# Relay-Board_Rack-PDU_2_1.net
KiCad netlist of a schematic drawn in EAGLE
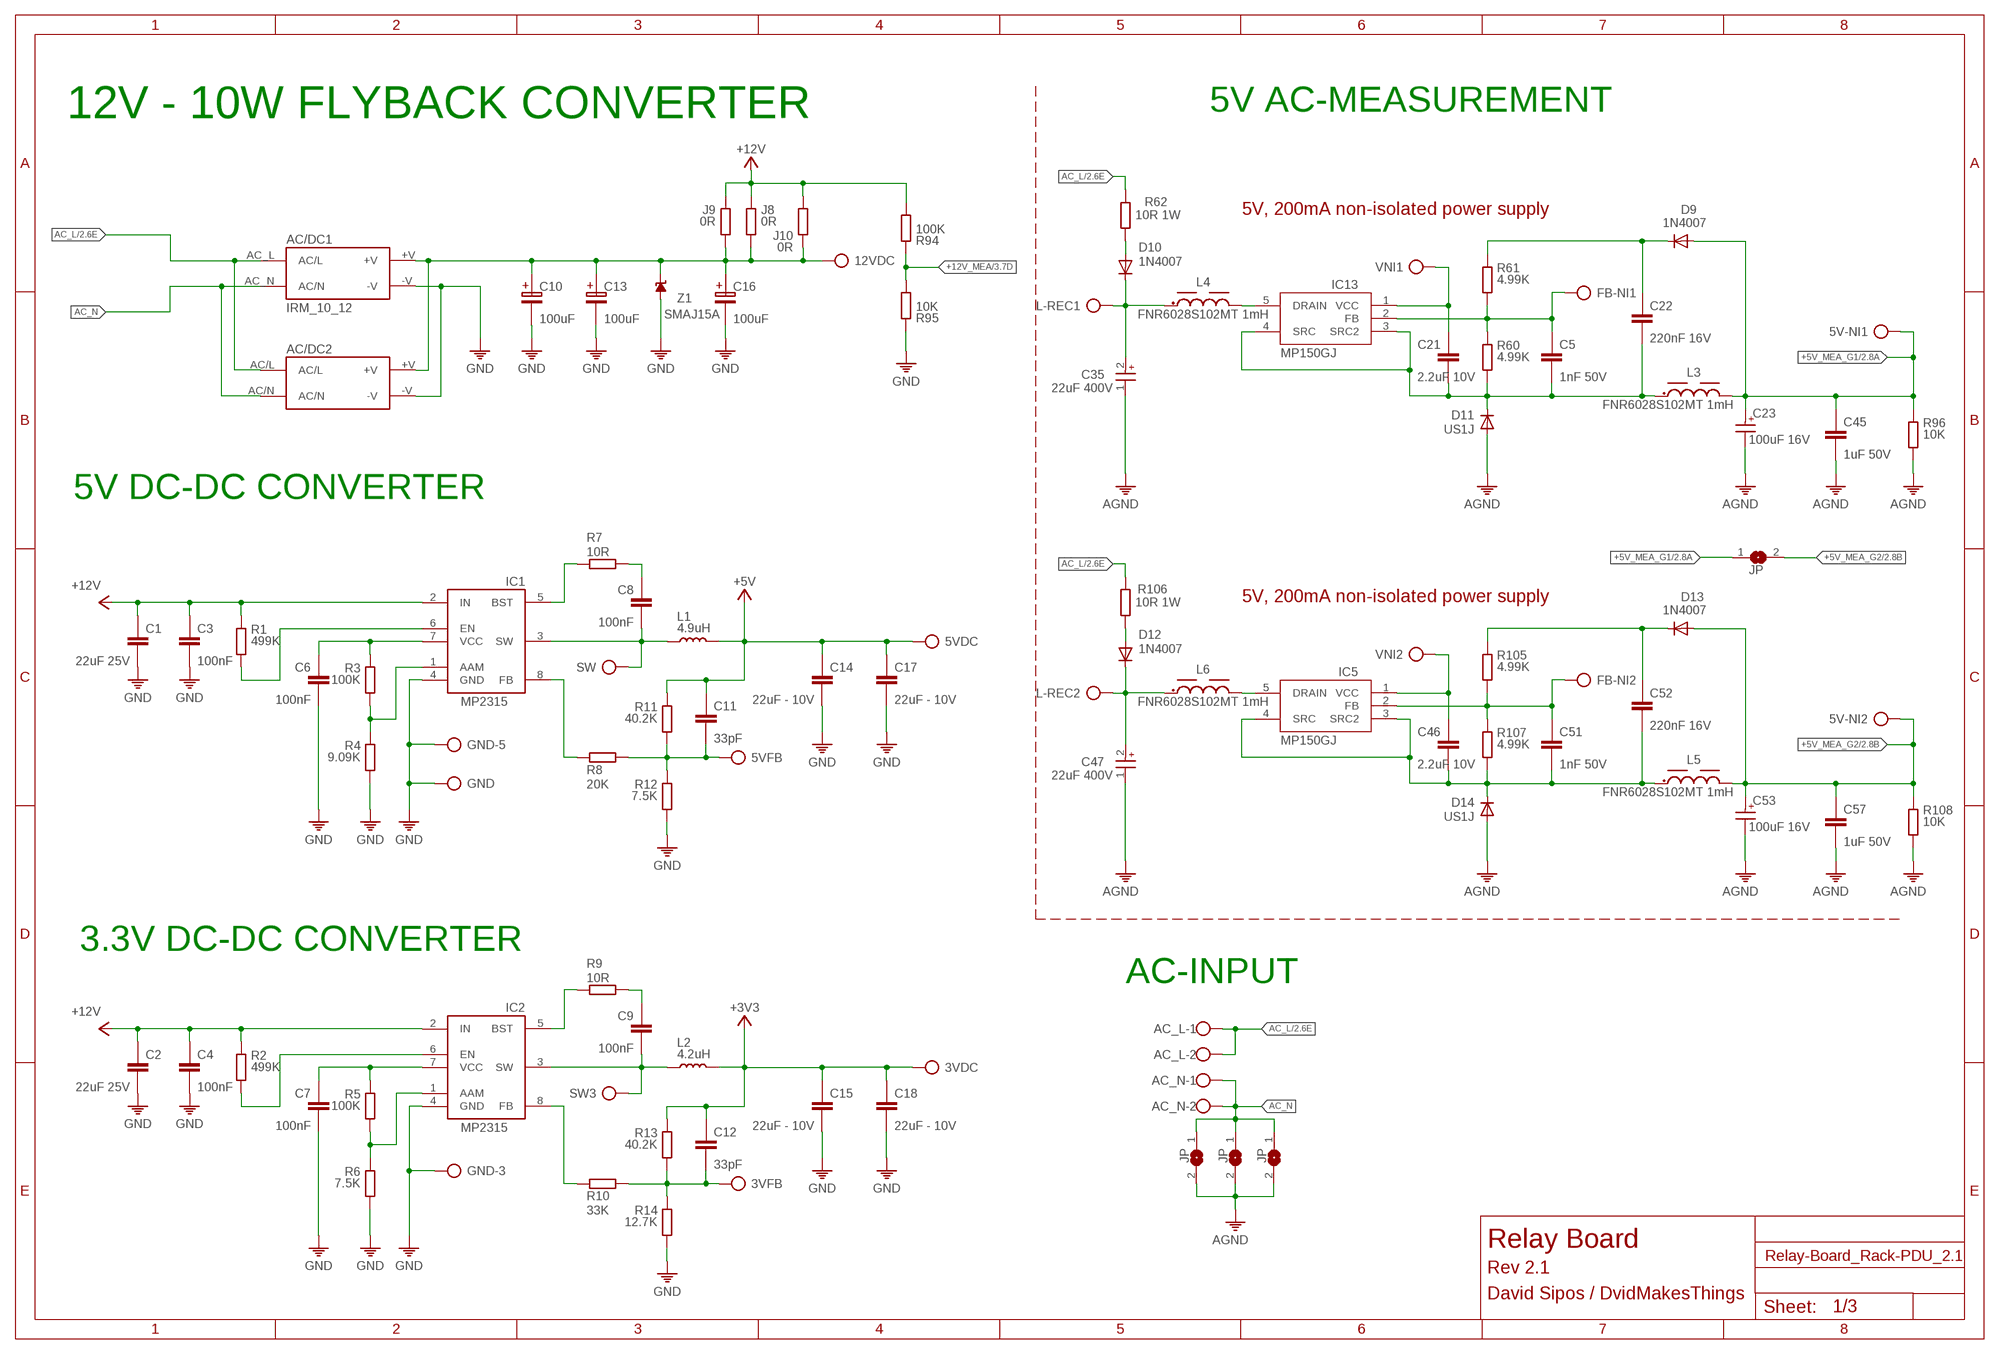
[diagram p0: schematic, sheet 1]
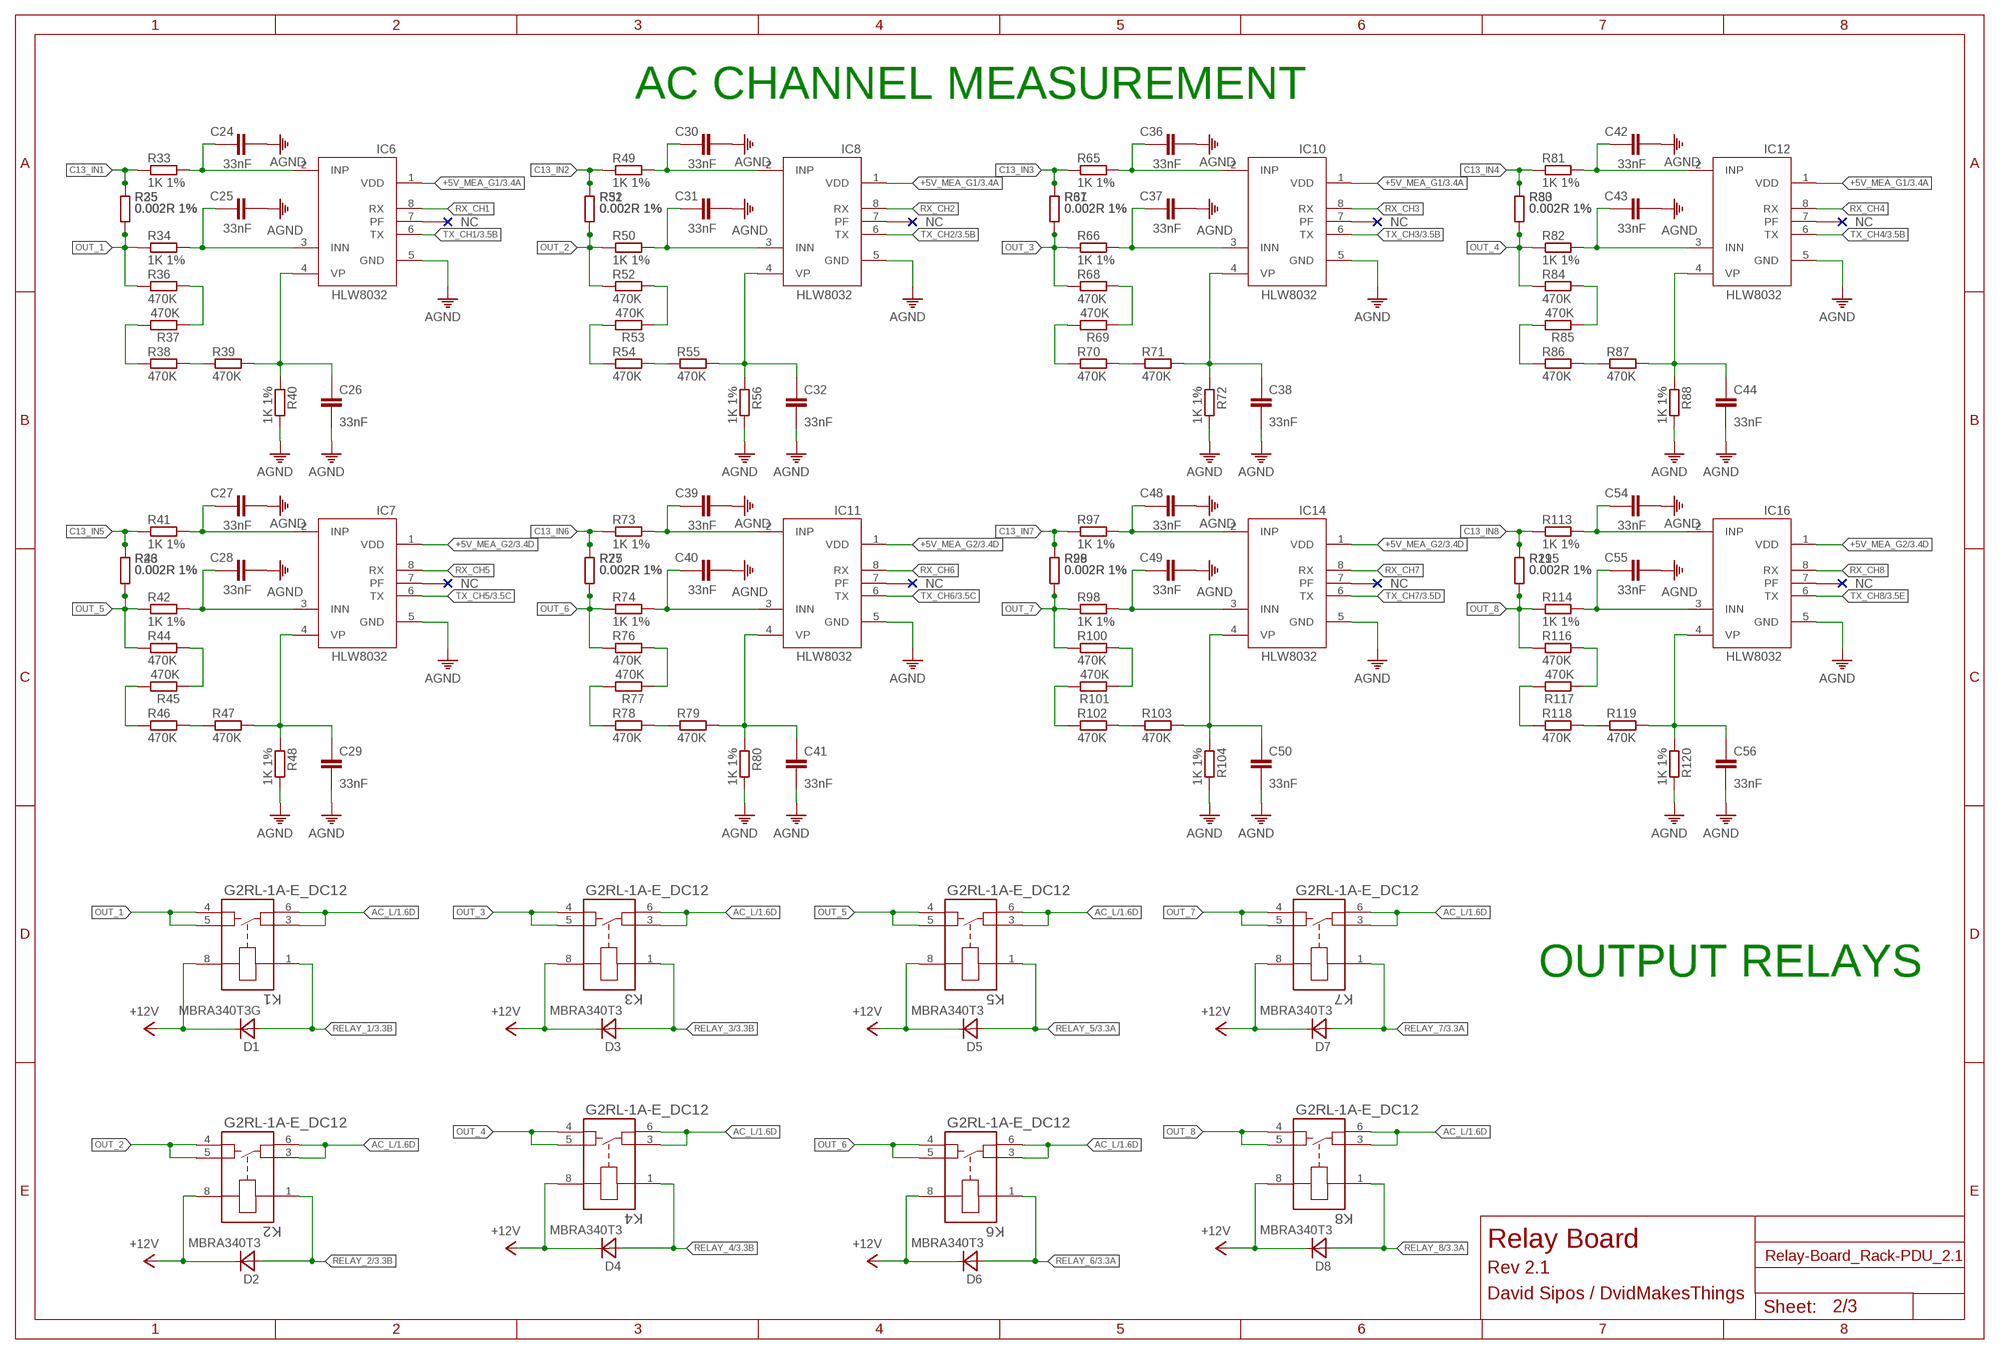
[diagram p1: schematic, sheet 2]
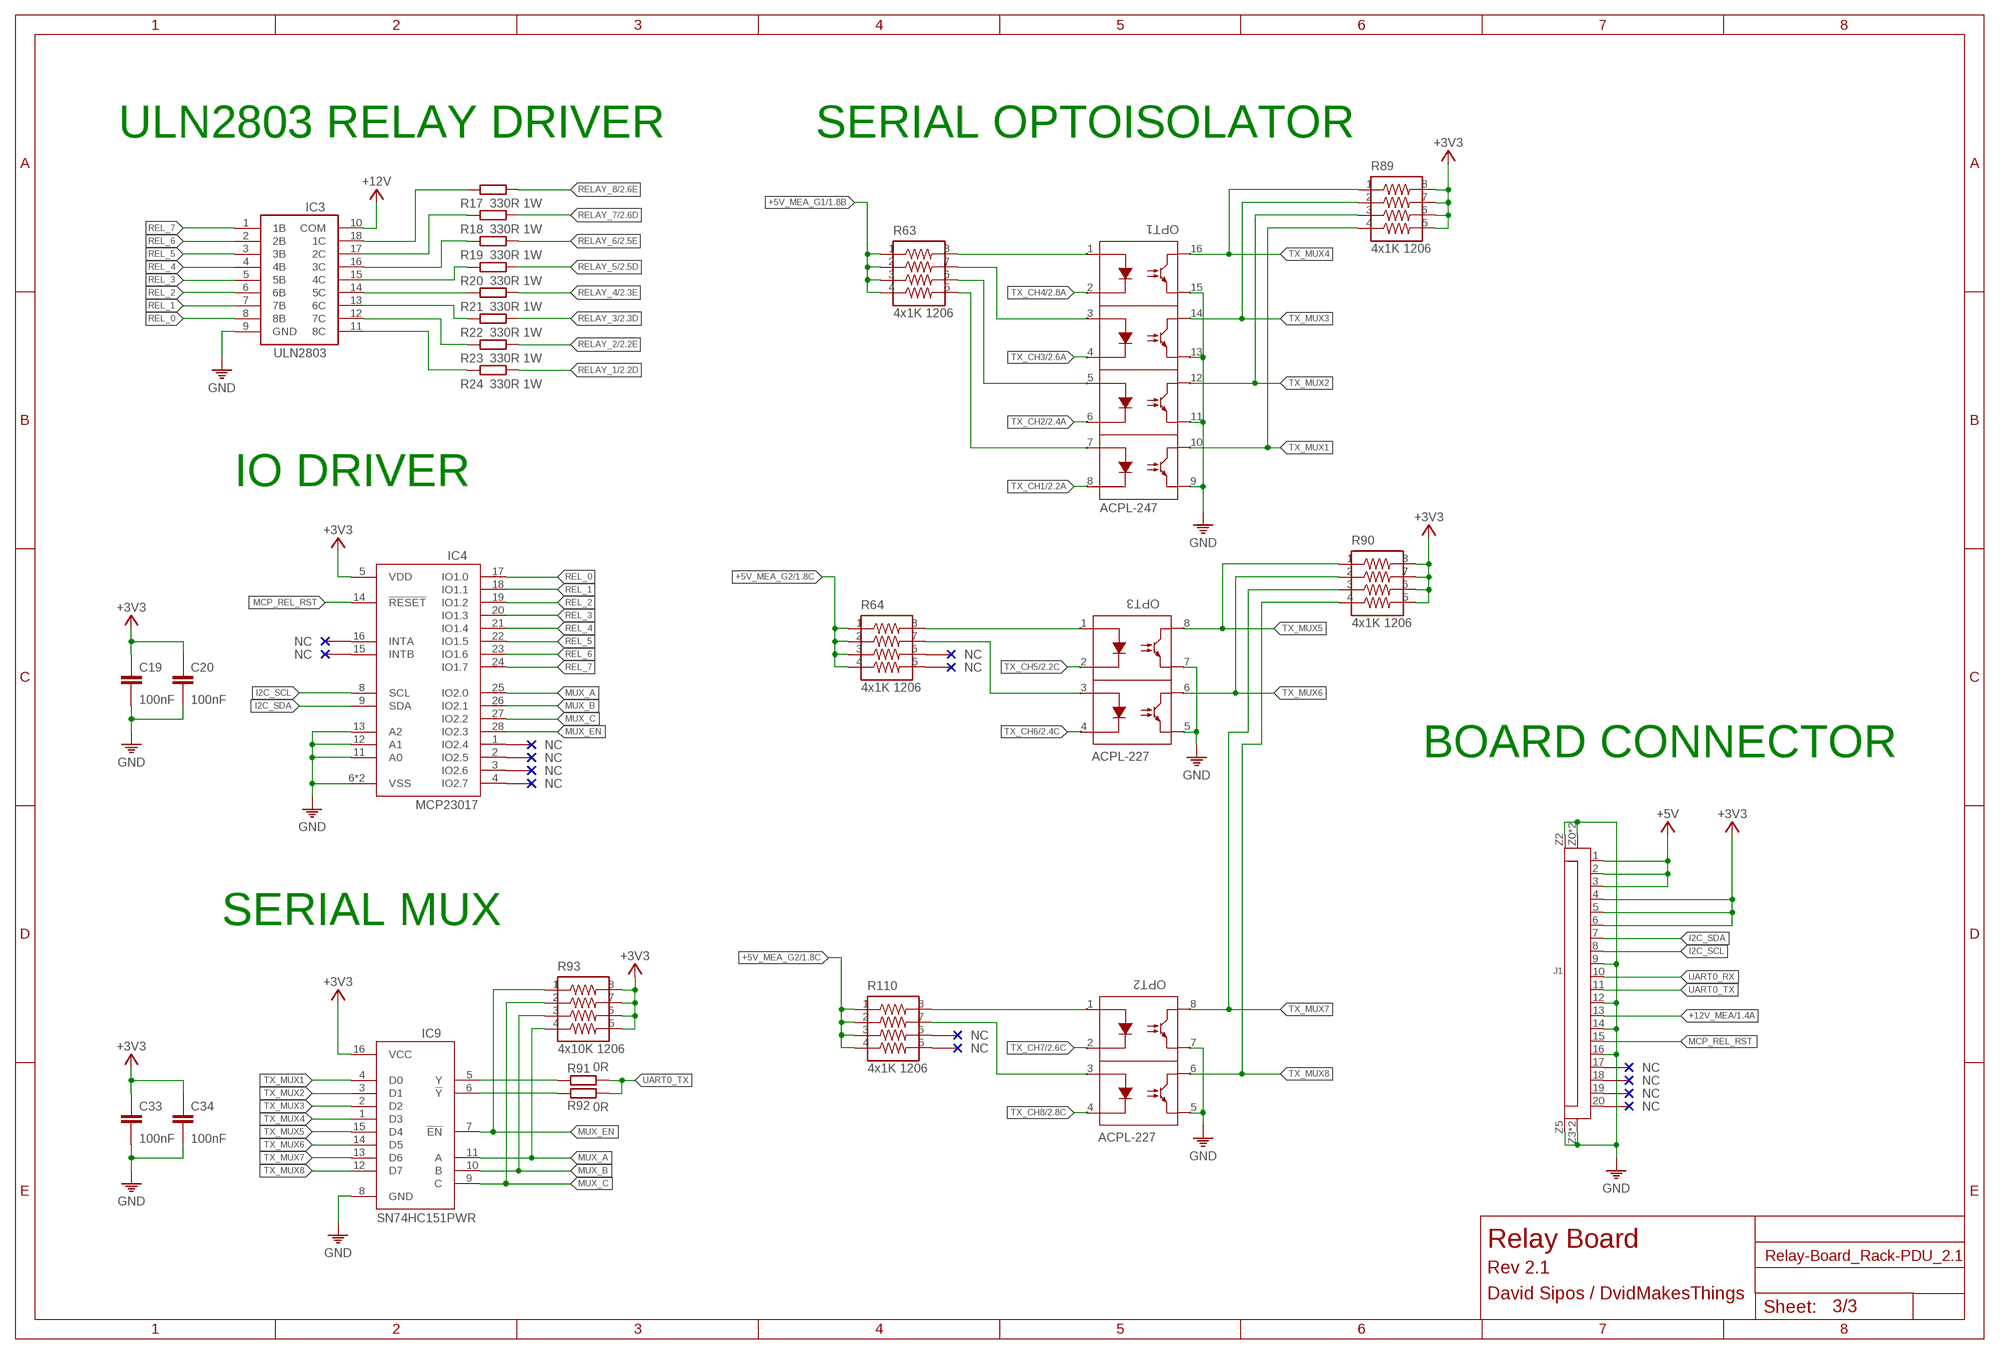
[diagram p2: schematic, sheet 3]

(export (version "E")
  (design (tool "Eeschema 10.0.6"))
  (components
    (comp (ref "C19")
      (value "100nF")
      (footprint "eagle-import:C0402")
      (libsource (lib "eagle-import") (part "C-0402"))
    )
    (comp (ref "C20")
      (value "100nF")
      (footprint "eagle-import:C0402")
      (libsource (lib "eagle-import") (part "C-0402"))
    )
    (comp (ref "C33")
      (value "100nF")
      (footprint "eagle-import:C0402")
      (libsource (lib "eagle-import") (part "C-0402"))
    )
    (comp (ref "C34")
      (value "100nF")
      (footprint "eagle-import:C0402")
      (libsource (lib "eagle-import") (part "C-0402"))
    )
    (comp (ref "IC3")
      (value "ULN2803A")
      (footprint "eagle-import:SO18")
      (libsource (lib "eagle-import") (part "ULN2803"))
    )
    (comp (ref "IC4")
      (value "MCP23017-E/ML")
      (footprint "eagle-import:QFN28[6X6]ML")
      (libsource (lib "eagle-import") (part "MCP23017-E/ML"))
    )
    (comp (ref "IC9")
      (value "SN74HC151PWR")
      (footprint "eagle-import:TSSOP16")
      (libsource (lib "eagle-import") (part "SN74HC151PWR"))
    )
    (comp (ref "J1")
      (value "FPC20-H")
      (footprint "eagle-import:FPC20")
      (libsource (lib "eagle-import") (part "FPC20-H"))
    )
    (comp (ref "OPT1")
      (value "ACPL-247")
      (footprint "eagle-import:SO16")
      (libsource (lib "eagle-import") (part "ACPL-2471"))
    )
    (comp (ref "OPT2")
      (value "ACPL-227")
      (footprint "eagle-import:SO8")
      (libsource (lib "eagle-import") (part "ACPL-227"))
    )
    (comp (ref "OPT3")
      (value "ACPL-227")
      (footprint "eagle-import:SO8")
      (libsource (lib "eagle-import") (part "ACPL-227"))
    )
    (comp (ref "R17")
      (value "330R 1W")
      (footprint "eagle-import:2512")
      (libsource (lib "eagle-import") (part "R2512"))
    )
    (comp (ref "R18")
      (value "330R 1W")
      (footprint "eagle-import:2512")
      (libsource (lib "eagle-import") (part "R2512"))
    )
    (comp (ref "R19")
      (value "330R 1W")
      (footprint "eagle-import:2512")
      (libsource (lib "eagle-import") (part "R2512"))
    )
    (comp (ref "R20")
      (value "330R 1W")
      (footprint "eagle-import:2512")
      (libsource (lib "eagle-import") (part "R2512"))
    )
    (comp (ref "R21")
      (value "330R 1W")
      (footprint "eagle-import:2512")
      (libsource (lib "eagle-import") (part "R2512"))
    )
    (comp (ref "R22")
      (value "330R 1W")
      (footprint "eagle-import:2512")
      (libsource (lib "eagle-import") (part "R2512"))
    )
    (comp (ref "R23")
      (value "330R 1W")
      (footprint "eagle-import:2512")
      (libsource (lib "eagle-import") (part "R2512"))
    )
    (comp (ref "R24")
      (value "330R 1W")
      (footprint "eagle-import:2512")
      (libsource (lib "eagle-import") (part "R2512"))
    )
    (comp (ref "R63")
      (value "4x1K 1206")
      (footprint "eagle-import:742C083103JP")
      (fields
        (field (name "MANUFACTURER") "CTS Resistor Products")
        (field (name "MPN") "742C083103JP")
        (field (name "CREATED_BY") "PCBLayout.com")
      )
      (libsource (lib "eagle-import") (part "742C083103JP"))
    )
    (comp (ref "R64")
      (value "4x1K 1206")
      (footprint "eagle-import:742C083103JP")
      (fields
        (field (name "MANUFACTURER") "CTS Resistor Products")
        (field (name "MPN") "742C083103JP")
        (field (name "CREATED_BY") "PCBLayout.com")
      )
      (libsource (lib "eagle-import") (part "742C083103JP"))
    )
    (comp (ref "R89")
      (value "4x1K 1206")
      (footprint "eagle-import:742C083103JP")
      (fields
        (field (name "MANUFACTURER") "CTS Resistor Products")
        (field (name "MPN") "742C083103JP")
        (field (name "CREATED_BY") "PCBLayout.com")
      )
      (libsource (lib "eagle-import") (part "742C083103JP"))
    )
    (comp (ref "R90")
      (value "4x1K 1206")
      (footprint "eagle-import:742C083103JP")
      (fields
        (field (name "MANUFACTURER") "CTS Resistor Products")
        (field (name "MPN") "742C083103JP")
        (field (name "CREATED_BY") "PCBLayout.com")
      )
      (libsource (lib "eagle-import") (part "742C083103JP"))
    )
    (comp (ref "R91")
      (value "0R")
      (footprint "eagle-import:0402")
      (libsource (lib "eagle-import") (part "R0402"))
    )
    (comp (ref "R92")
      (value "0R")
      (footprint "eagle-import:0402")
      (libsource (lib "eagle-import") (part "R0402"))
    )
    (comp (ref "R93")
      (value "4x10K 1206")
      (footprint "eagle-import:742C083103JP")
      (fields
        (field (name "MANUFACTURER") "CTS Resistor Products")
        (field (name "MPN") "742C083103JP")
        (field (name "CREATED_BY") "PCBLayout.com")
      )
      (libsource (lib "eagle-import") (part "742C083103JP"))
    )
    (comp (ref "R110")
      (value "4x1K 1206")
      (footprint "eagle-import:742C083103JP")
      (fields
        (field (name "MANUFACTURER") "CTS Resistor Products")
        (field (name "MPN") "742C083103JP")
        (field (name "CREATED_BY") "PCBLayout.com")
      )
      (libsource (lib "eagle-import") (part "742C083103JP"))
    )
    (comp (ref "C24")
      (value "33nF")
      (footprint "eagle-import:C1206")
      (libsource (lib "eagle-import") (part "C-1206"))
    )
    (comp (ref "C25")
      (value "33nF")
      (footprint "eagle-import:C1206")
      (libsource (lib "eagle-import") (part "C-1206"))
    )
    (comp (ref "C26")
      (value "33nF")
      (footprint "eagle-import:C1206")
      (libsource (lib "eagle-import") (part "C-1206"))
    )
    (comp (ref "C27")
      (value "33nF")
      (footprint "eagle-import:C1206")
      (libsource (lib "eagle-import") (part "C-1206"))
    )
    (comp (ref "C28")
      (value "33nF")
      (footprint "eagle-import:C1206")
      (libsource (lib "eagle-import") (part "C-1206"))
    )
    (comp (ref "C29")
      (value "33nF")
      (footprint "eagle-import:C1206")
      (libsource (lib "eagle-import") (part "C-1206"))
    )
    (comp (ref "C30")
      (value "33nF")
      (footprint "eagle-import:C1206")
      (libsource (lib "eagle-import") (part "C-1206"))
    )
    (comp (ref "C31")
      (value "33nF")
      (footprint "eagle-import:C1206")
      (libsource (lib "eagle-import") (part "C-1206"))
    )
    (comp (ref "C32")
      (value "33nF")
      (footprint "eagle-import:C1206")
      (libsource (lib "eagle-import") (part "C-1206"))
    )
    (comp (ref "C36")
      (value "33nF")
      (footprint "eagle-import:C1206")
      (libsource (lib "eagle-import") (part "C-1206"))
    )
    (comp (ref "C37")
      (value "33nF")
      (footprint "eagle-import:C1206")
      (libsource (lib "eagle-import") (part "C-1206"))
    )
    (comp (ref "C38")
      (value "33nF")
      (footprint "eagle-import:C1206")
      (libsource (lib "eagle-import") (part "C-1206"))
    )
    (comp (ref "C39")
      (value "33nF")
      (footprint "eagle-import:C1206")
      (libsource (lib "eagle-import") (part "C-1206"))
    )
    (comp (ref "C40")
      (value "33nF")
      (footprint "eagle-import:C1206")
      (libsource (lib "eagle-import") (part "C-1206"))
    )
    (comp (ref "C41")
      (value "33nF")
      (footprint "eagle-import:C1206")
      (libsource (lib "eagle-import") (part "C-1206"))
    )
    (comp (ref "C42")
      (value "33nF")
      (footprint "eagle-import:C1206")
      (libsource (lib "eagle-import") (part "C-1206"))
    )
    (comp (ref "C43")
      (value "33nF")
      (footprint "eagle-import:C1206")
      (libsource (lib "eagle-import") (part "C-1206"))
    )
    (comp (ref "C44")
      (value "33nF")
      (footprint "eagle-import:C1206")
      (libsource (lib "eagle-import") (part "C-1206"))
    )
    (comp (ref "C48")
      (value "33nF")
      (footprint "eagle-import:C1206")
      (libsource (lib "eagle-import") (part "C-1206"))
    )
    (comp (ref "C49")
      (value "33nF")
      (footprint "eagle-import:C1206")
      (libsource (lib "eagle-import") (part "C-1206"))
    )
    (comp (ref "C50")
      (value "33nF")
      (footprint "eagle-import:C1206")
      (libsource (lib "eagle-import") (part "C-1206"))
    )
    (comp (ref "C54")
      (value "33nF")
      (footprint "eagle-import:C1206")
      (libsource (lib "eagle-import") (part "C-1206"))
    )
    (comp (ref "C55")
      (value "33nF")
      (footprint "eagle-import:C1206")
      (libsource (lib "eagle-import") (part "C-1206"))
    )
    (comp (ref "C56")
      (value "33nF")
      (footprint "eagle-import:C1206")
      (libsource (lib "eagle-import") (part "C-1206"))
    )
    (comp (ref "D1")
      (value "MBRA340T3G")
      (footprint "eagle-import:SMA")
      (libsource (lib "eagle-import") (part "MBRA340T3"))
    )
    (comp (ref "D2")
      (value "MBRA340T3")
      (footprint "eagle-import:SMA")
      (libsource (lib "eagle-import") (part "MBRA340T3"))
    )
    (comp (ref "D3")
      (value "MBRA340T3")
      (footprint "eagle-import:SMA")
      (libsource (lib "eagle-import") (part "MBRA340T3"))
    )
    (comp (ref "D4")
      (value "MBRA340T3")
      (footprint "eagle-import:SMA")
      (libsource (lib "eagle-import") (part "MBRA340T3"))
    )
    (comp (ref "D5")
      (value "MBRA340T3")
      (footprint "eagle-import:SMA")
      (libsource (lib "eagle-import") (part "MBRA340T3"))
    )
    (comp (ref "D6")
      (value "MBRA340T3")
      (footprint "eagle-import:SMA")
      (libsource (lib "eagle-import") (part "MBRA340T3"))
    )
    (comp (ref "D7")
      (value "MBRA340T3")
      (footprint "eagle-import:SMA")
      (libsource (lib "eagle-import") (part "MBRA340T3"))
    )
    (comp (ref "D8")
      (value "MBRA340T3")
      (footprint "eagle-import:SMA")
      (libsource (lib "eagle-import") (part "MBRA340T3"))
    )
    (comp (ref "IC6")
      (value "HLW8032")
      (footprint "eagle-import:SO8")
      (libsource (lib "eagle-import") (part "HLW8032"))
    )
    (comp (ref "IC7")
      (value "HLW8032")
      (footprint "eagle-import:SO8")
      (libsource (lib "eagle-import") (part "HLW8032"))
    )
    (comp (ref "IC8")
      (value "HLW8032")
      (footprint "eagle-import:SO8")
      (libsource (lib "eagle-import") (part "HLW8032"))
    )
    (comp (ref "IC10")
      (value "HLW8032")
      (footprint "eagle-import:SO8")
      (libsource (lib "eagle-import") (part "HLW8032"))
    )
    (comp (ref "IC11")
      (value "HLW8032")
      (footprint "eagle-import:SO8")
      (libsource (lib "eagle-import") (part "HLW8032"))
    )
    (comp (ref "IC12")
      (value "HLW8032")
      (footprint "eagle-import:SO8")
      (libsource (lib "eagle-import") (part "HLW8032"))
    )
    (comp (ref "IC14")
      (value "HLW8032")
      (footprint "eagle-import:SO8")
      (libsource (lib "eagle-import") (part "HLW8032"))
    )
    (comp (ref "IC16")
      (value "HLW8032")
      (footprint "eagle-import:SO8")
      (libsource (lib "eagle-import") (part "HLW8032"))
    )
    (comp (ref "K1")
      (value "G2RL-1A-E_DC12")
      (footprint "eagle-import:RELAY_G2RL-1A-E_DC5_OMR")
      (fields
        (field (name "MANUFACTURER_PART_NUMBER") "G2RL-1A-E DC12")
        (field (name "COPYRIGHT") "Copyright (C) 2025 Ultra Librarian. All rights reserved.")
      )
      (libsource (lib "eagle-import") (part "G2RL-1A-E_DC12"))
    )
    (comp (ref "K2")
      (value "G2RL-1A-E_DC12")
      (footprint "eagle-import:RELAY_G2RL-1A-E_DC5_OMR")
      (fields
        (field (name "MANUFACTURER_PART_NUMBER") "G2RL-1A-E DC12")
        (field (name "COPYRIGHT") "Copyright (C) 2025 Ultra Librarian. All rights reserved.")
      )
      (libsource (lib "eagle-import") (part "G2RL-1A-E_DC12"))
    )
    (comp (ref "K3")
      (value "G2RL-1A-E_DC12")
      (footprint "eagle-import:RELAY_G2RL-1A-E_DC5_OMR")
      (fields
        (field (name "MANUFACTURER_PART_NUMBER") "G2RL-1A-E DC12")
        (field (name "COPYRIGHT") "Copyright (C) 2025 Ultra Librarian. All rights reserved.")
      )
      (libsource (lib "eagle-import") (part "G2RL-1A-E_DC12"))
    )
    (comp (ref "K4")
      (value "G2RL-1A-E_DC12")
      (footprint "eagle-import:RELAY_G2RL-1A-E_DC5_OMR")
      (fields
        (field (name "MANUFACTURER_PART_NUMBER") "G2RL-1A-E DC12")
        (field (name "COPYRIGHT") "Copyright (C) 2025 Ultra Librarian. All rights reserved.")
      )
      (libsource (lib "eagle-import") (part "G2RL-1A-E_DC12"))
    )
    (comp (ref "K5")
      (value "G2RL-1A-E_DC12")
      (footprint "eagle-import:RELAY_G2RL-1A-E_DC5_OMR")
      (fields
        (field (name "MANUFACTURER_PART_NUMBER") "G2RL-1A-E DC12")
        (field (name "COPYRIGHT") "Copyright (C) 2025 Ultra Librarian. All rights reserved.")
      )
      (libsource (lib "eagle-import") (part "G2RL-1A-E_DC12"))
    )
    (comp (ref "K6")
      (value "G2RL-1A-E_DC12")
      (footprint "eagle-import:RELAY_G2RL-1A-E_DC5_OMR")
      (fields
        (field (name "MANUFACTURER_PART_NUMBER") "G2RL-1A-E DC12")
        (field (name "COPYRIGHT") "Copyright (C) 2025 Ultra Librarian. All rights reserved.")
      )
      (libsource (lib "eagle-import") (part "G2RL-1A-E_DC12"))
    )
    (comp (ref "K7")
      (value "G2RL-1A-E_DC12")
      (footprint "eagle-import:RELAY_G2RL-1A-E_DC5_OMR")
      (fields
        (field (name "MANUFACTURER_PART_NUMBER") "G2RL-1A-E DC12")
        (field (name "COPYRIGHT") "Copyright (C) 2025 Ultra Librarian. All rights reserved.")
      )
      (libsource (lib "eagle-import") (part "G2RL-1A-E_DC12"))
    )
    (comp (ref "K8")
      (value "G2RL-1A-E_DC12")
      (footprint "eagle-import:RELAY_G2RL-1A-E_DC5_OMR")
      (fields
        (field (name "MANUFACTURER_PART_NUMBER") "G2RL-1A-E DC12")
        (field (name "COPYRIGHT") "Copyright (C) 2025 Ultra Librarian. All rights reserved.")
      )
      (libsource (lib "eagle-import") (part "G2RL-1A-E_DC12"))
    )
    (comp (ref "R25")
      (value "0.002R 1%")
      (footprint "eagle-import:2512")
      (libsource (lib "eagle-import") (part "R2512"))
    )
    (comp (ref "R26")
      (value "0.002R 1%")
      (footprint "eagle-import:2512")
      (libsource (lib "eagle-import") (part "R2512"))
    )
    (comp (ref "R27")
      (value "0.002R 1%")
      (footprint "eagle-import:2512")
      (libsource (lib "eagle-import") (part "R2512"))
    )
    (comp (ref "R28")
      (value "0.002R 1%")
      (footprint "eagle-import:2512")
      (libsource (lib "eagle-import") (part "R2512"))
    )
    (comp (ref "R29")
      (value "0.002R 1%")
      (footprint "eagle-import:2512")
      (libsource (lib "eagle-import") (part "R2512"))
    )
    (comp (ref "R30")
      (value "0.002R 1%")
      (footprint "eagle-import:2512")
      (libsource (lib "eagle-import") (part "R2512"))
    )
    (comp (ref "R31")
      (value "0.002R 1%")
      (footprint "eagle-import:2512")
      (libsource (lib "eagle-import") (part "R2512"))
    )
    (comp (ref "R32")
      (value "0.002R 1%")
      (footprint "eagle-import:2512")
      (libsource (lib "eagle-import") (part "R2512"))
    )
    (comp (ref "R33")
      (value "1K 1%")
      (footprint "eagle-import:1206")
      (libsource (lib "eagle-import") (part "R1206"))
    )
    (comp (ref "R34")
      (value "1K 1%")
      (footprint "eagle-import:1206")
      (libsource (lib "eagle-import") (part "R1206"))
    )
    (comp (ref "R35")
      (value "0.002R 1%")
      (footprint "eagle-import:2512")
      (libsource (lib "eagle-import") (part "R2512"))
    )
    (comp (ref "R36")
      (value "470K")
      (footprint "eagle-import:1206")
      (libsource (lib "eagle-import") (part "R1206"))
    )
    (comp (ref "R37")
      (value "470K")
      (footprint "eagle-import:1206")
      (libsource (lib "eagle-import") (part "R1206"))
    )
    (comp (ref "R38")
      (value "470K")
      (footprint "eagle-import:1206")
      (libsource (lib "eagle-import") (part "R1206"))
    )
    (comp (ref "R39")
      (value "470K")
      (footprint "eagle-import:1206")
      (libsource (lib "eagle-import") (part "R1206"))
    )
    (comp (ref "R40")
      (value "1K 1%")
      (footprint "eagle-import:1206")
      (libsource (lib "eagle-import") (part "R1206"))
    )
    (comp (ref "R41")
      (value "1K 1%")
      (footprint "eagle-import:1206")
      (libsource (lib "eagle-import") (part "R1206"))
    )
    (comp (ref "R42")
      (value "1K 1%")
      (footprint "eagle-import:1206")
      (libsource (lib "eagle-import") (part "R1206"))
    )
    (comp (ref "R43")
      (value "0.002R 1%")
      (footprint "eagle-import:2512")
      (libsource (lib "eagle-import") (part "R2512"))
    )
    (comp (ref "R44")
      (value "470K")
      (footprint "eagle-import:1206")
      (libsource (lib "eagle-import") (part "R1206"))
    )
    (comp (ref "R45")
      (value "470K")
      (footprint "eagle-import:1206")
      (libsource (lib "eagle-import") (part "R1206"))
    )
    (comp (ref "R46")
      (value "470K")
      (footprint "eagle-import:1206")
      (libsource (lib "eagle-import") (part "R1206"))
    )
    (comp (ref "R47")
      (value "470K")
      (footprint "eagle-import:1206")
      (libsource (lib "eagle-import") (part "R1206"))
    )
    (comp (ref "R48")
      (value "1K 1%")
      (footprint "eagle-import:1206")
      (libsource (lib "eagle-import") (part "R1206"))
    )
    (comp (ref "R49")
      (value "1K 1%")
      (footprint "eagle-import:1206")
      (libsource (lib "eagle-import") (part "R1206"))
    )
    (comp (ref "R50")
      (value "1K 1%")
      (footprint "eagle-import:1206")
      (libsource (lib "eagle-import") (part "R1206"))
    )
    (comp (ref "R51")
      (value "0.002R 1%")
      (footprint "eagle-import:2512")
      (libsource (lib "eagle-import") (part "R2512"))
    )
    (comp (ref "R52")
      (value "470K")
      (footprint "eagle-import:1206")
      (libsource (lib "eagle-import") (part "R1206"))
    )
    (comp (ref "R53")
      (value "470K")
      (footprint "eagle-import:1206")
      (libsource (lib "eagle-import") (part "R1206"))
    )
    (comp (ref "R54")
      (value "470K")
      (footprint "eagle-import:1206")
      (libsource (lib "eagle-import") (part "R1206"))
    )
    (comp (ref "R55")
      (value "470K")
      (footprint "eagle-import:1206")
      (libsource (lib "eagle-import") (part "R1206"))
    )
    (comp (ref "R56")
      (value "1K 1%")
      (footprint "eagle-import:1206")
      (libsource (lib "eagle-import") (part "R1206"))
    )
    (comp (ref "R65")
      (value "1K 1%")
      (footprint "eagle-import:1206")
      (libsource (lib "eagle-import") (part "R1206"))
    )
    (comp (ref "R66")
      (value "1K 1%")
      (footprint "eagle-import:1206")
      (libsource (lib "eagle-import") (part "R1206"))
    )
    (comp (ref "R67")
      (value "0.002R 1%")
      (footprint "eagle-import:2512")
      (libsource (lib "eagle-import") (part "R2512"))
    )
    (comp (ref "R68")
      (value "470K")
      (footprint "eagle-import:1206")
      (libsource (lib "eagle-import") (part "R1206"))
    )
    (comp (ref "R69")
      (value "470K")
      (footprint "eagle-import:1206")
      (libsource (lib "eagle-import") (part "R1206"))
    )
    (comp (ref "R70")
      (value "470K")
      (footprint "eagle-import:1206")
      (libsource (lib "eagle-import") (part "R1206"))
    )
    (comp (ref "R71")
      (value "470K")
      (footprint "eagle-import:1206")
      (libsource (lib "eagle-import") (part "R1206"))
    )
    (comp (ref "R72")
      (value "1K 1%")
      (footprint "eagle-import:1206")
      (libsource (lib "eagle-import") (part "R1206"))
    )
    (comp (ref "R73")
      (value "1K 1%")
      (footprint "eagle-import:1206")
      (libsource (lib "eagle-import") (part "R1206"))
    )
    (comp (ref "R74")
      (value "1K 1%")
      (footprint "eagle-import:1206")
      (libsource (lib "eagle-import") (part "R1206"))
    )
    (comp (ref "R75")
      (value "0.002R 1%")
      (footprint "eagle-import:2512")
      (libsource (lib "eagle-import") (part "R2512"))
    )
    (comp (ref "R76")
      (value "470K")
      (footprint "eagle-import:1206")
      (libsource (lib "eagle-import") (part "R1206"))
    )
    (comp (ref "R77")
      (value "470K")
      (footprint "eagle-import:1206")
      (libsource (lib "eagle-import") (part "R1206"))
    )
    (comp (ref "R78")
      (value "470K")
      (footprint "eagle-import:1206")
      (libsource (lib "eagle-import") (part "R1206"))
    )
    (comp (ref "R79")
      (value "470K")
      (footprint "eagle-import:1206")
      (libsource (lib "eagle-import") (part "R1206"))
    )
    (comp (ref "R80")
      (value "1K 1%")
      (footprint "eagle-import:1206")
      (libsource (lib "eagle-import") (part "R1206"))
    )
    (comp (ref "R81")
      (value "1K 1%")
      (footprint "eagle-import:1206")
      (libsource (lib "eagle-import") (part "R1206"))
    )
    (comp (ref "R82")
      (value "1K 1%")
      (footprint "eagle-import:1206")
      (libsource (lib "eagle-import") (part "R1206"))
    )
    (comp (ref "R83")
      (value "0.002R 1%")
      (footprint "eagle-import:2512")
      (libsource (lib "eagle-import") (part "R2512"))
    )
    (comp (ref "R84")
      (value "470K")
      (footprint "eagle-import:1206")
      (libsource (lib "eagle-import") (part "R1206"))
    )
    (comp (ref "R85")
      (value "470K")
      (footprint "eagle-import:1206")
      (libsource (lib "eagle-import") (part "R1206"))
    )
    (comp (ref "R86")
      (value "470K")
      (footprint "eagle-import:1206")
      (libsource (lib "eagle-import") (part "R1206"))
    )
    (comp (ref "R87")
      (value "470K")
      (footprint "eagle-import:1206")
      (libsource (lib "eagle-import") (part "R1206"))
    )
    (comp (ref "R88")
      (value "1K 1%")
      (footprint "eagle-import:1206")
      (libsource (lib "eagle-import") (part "R1206"))
    )
    (comp (ref "R97")
      (value "1K 1%")
      (footprint "eagle-import:1206")
      (libsource (lib "eagle-import") (part "R1206"))
    )
    (comp (ref "R98")
      (value "1K 1%")
      (footprint "eagle-import:1206")
      (libsource (lib "eagle-import") (part "R1206"))
    )
    (comp (ref "R99")
      (value "0.002R 1%")
      (footprint "eagle-import:2512")
      (libsource (lib "eagle-import") (part "R2512"))
    )
    (comp (ref "R100")
      (value "470K")
      (footprint "eagle-import:1206")
      (libsource (lib "eagle-import") (part "R1206"))
    )
    (comp (ref "R101")
      (value "470K")
      (footprint "eagle-import:1206")
      (libsource (lib "eagle-import") (part "R1206"))
    )
    (comp (ref "R102")
      (value "470K")
      (footprint "eagle-import:1206")
      (libsource (lib "eagle-import") (part "R1206"))
    )
    (comp (ref "R103")
      (value "470K")
      (footprint "eagle-import:1206")
      (libsource (lib "eagle-import") (part "R1206"))
    )
    (comp (ref "R104")
      (value "1K 1%")
      (footprint "eagle-import:1206")
      (libsource (lib "eagle-import") (part "R1206"))
    )
    (comp (ref "R113")
      (value "1K 1%")
      (footprint "eagle-import:1206")
      (libsource (lib "eagle-import") (part "R1206"))
    )
    (comp (ref "R114")
      (value "1K 1%")
      (footprint "eagle-import:1206")
      (libsource (lib "eagle-import") (part "R1206"))
    )
    (comp (ref "R115")
      (value "0.002R 1%")
      (footprint "eagle-import:2512")
      (libsource (lib "eagle-import") (part "R2512"))
    )
    (comp (ref "R116")
      (value "470K")
      (footprint "eagle-import:1206")
      (libsource (lib "eagle-import") (part "R1206"))
    )
    (comp (ref "R117")
      (value "470K")
      (footprint "eagle-import:1206")
      (libsource (lib "eagle-import") (part "R1206"))
    )
    (comp (ref "R118")
      (value "470K")
      (footprint "eagle-import:1206")
      (libsource (lib "eagle-import") (part "R1206"))
    )
    (comp (ref "R119")
      (value "470K")
      (footprint "eagle-import:1206")
      (libsource (lib "eagle-import") (part "R1206"))
    )
    (comp (ref "R120")
      (value "1K 1%")
      (footprint "eagle-import:1206")
      (libsource (lib "eagle-import") (part "R1206"))
    )
    (comp (ref "3VDC")
      (value "TP")
      (footprint "eagle-import:TP")
      (libsource (lib "eagle-import") (part "TP"))
    )
    (comp (ref "3VFB")
      (value "TP")
      (footprint "eagle-import:TP")
      (libsource (lib "eagle-import") (part "TP"))
    )
    (comp (ref "5V-NI1")
      (value "TP")
      (footprint "eagle-import:TP")
      (libsource (lib "eagle-import") (part "TP"))
    )
    (comp (ref "5V-NI2")
      (value "TP")
      (footprint "eagle-import:TP")
      (libsource (lib "eagle-import") (part "TP"))
    )
    (comp (ref "5VDC")
      (value "TP")
      (footprint "eagle-import:TP")
      (libsource (lib "eagle-import") (part "TP"))
    )
    (comp (ref "5VFB")
      (value "TP")
      (footprint "eagle-import:TP")
      (libsource (lib "eagle-import") (part "TP"))
    )
    (comp (ref "12VDC")
      (value "TP")
      (footprint "eagle-import:TP")
      (libsource (lib "eagle-import") (part "TP"))
    )
    (comp (ref "AC/DC1")
      (value "IRM_10_12")
      (footprint "eagle-import:IRM_10_12")
      (libsource (lib "eagle-import") (part "IRM_10_12"))
    )
    (comp (ref "AC/DC2")
      (value "IRM_10_12-2")
      (footprint "eagle-import:IRM_15_12")
      (libsource (lib "eagle-import") (part "IRM_10_12-2"))
    )
    (comp (ref "AC_L")
      (value "W237-102")
      (footprint "eagle-import:W237-102")
      (fields (field (name "MPN") "237-102"))
      (libsource (lib "eagle-import") (part "W237-102"))
    )
    (comp (ref "AC_N")
      (value "W237-102")
      (footprint "eagle-import:W237-102")
      (fields (field (name "MPN") "237-102"))
      (libsource (lib "eagle-import") (part "W237-102"))
    )
    (comp (ref "C1")
      (value "22uF 25V")
      (footprint "eagle-import:C1206")
      (libsource (lib "eagle-import") (part "C-1206"))
    )
    (comp (ref "C2")
      (value "22uF 25V")
      (footprint "eagle-import:C1206")
      (libsource (lib "eagle-import") (part "C-1206"))
    )
    (comp (ref "C3")
      (value "100nF")
      (footprint "eagle-import:0402")
      (libsource (lib "eagle-import") (part "C0402"))
    )
    (comp (ref "C4")
      (value "100nF")
      (footprint "eagle-import:0402")
      (libsource (lib "eagle-import") (part "C0402"))
    )
    (comp (ref "C5")
      (value "1nF 50V")
      (footprint "eagle-import:C0603")
      (libsource (lib "eagle-import") (part "C-0603"))
    )
    (comp (ref "C6")
      (value "100nF")
      (footprint "eagle-import:0402")
      (libsource (lib "eagle-import") (part "C0402"))
    )
    (comp (ref "C7")
      (value "100nF")
      (footprint "eagle-import:0402")
      (libsource (lib "eagle-import") (part "C0402"))
    )
    (comp (ref "C8")
      (value "100nF")
      (footprint "eagle-import:0402")
      (libsource (lib "eagle-import") (part "C0402"))
    )
    (comp (ref "C9")
      (value "100nF")
      (footprint "eagle-import:0402")
      (libsource (lib "eagle-import") (part "C0402"))
    )
    (comp (ref "C10")
      (value "100uF")
      (footprint "eagle-import:100UF-16V")
      (libsource (lib "eagle-import") (part "CPOL"))
    )
    (comp (ref "C11")
      (value "33pF")
      (footprint "eagle-import:0402")
      (libsource (lib "eagle-import") (part "C0402"))
    )
    (comp (ref "C12")
      (value "33pF")
      (footprint "eagle-import:0402")
      (libsource (lib "eagle-import") (part "C0402"))
    )
    (comp (ref "C13")
      (value "100uF")
      (footprint "eagle-import:100UF-16V")
      (libsource (lib "eagle-import") (part "CPOL"))
    )
    (comp (ref "C14")
      (value "22uF - 10V")
      (footprint "eagle-import:C1206")
      (libsource (lib "eagle-import") (part "C-1206"))
    )
    (comp (ref "C15")
      (value "22uF - 10V")
      (footprint "eagle-import:C1206")
      (libsource (lib "eagle-import") (part "C-1206"))
    )
    (comp (ref "C16")
      (value "100uF")
      (footprint "eagle-import:100UF-16V")
      (libsource (lib "eagle-import") (part "CPOL"))
    )
    (comp (ref "C17")
      (value "22uF - 10V")
      (footprint "eagle-import:C1206")
      (libsource (lib "eagle-import") (part "C-1206"))
    )
    (comp (ref "C18")
      (value "22uF - 10V")
      (footprint "eagle-import:C1206")
      (libsource (lib "eagle-import") (part "C-1206"))
    )
    (comp (ref "C21")
      (value "2.2uF 10V")
      (footprint "eagle-import:C0603")
      (libsource (lib "eagle-import") (part "C-0603"))
    )
    (comp (ref "C22")
      (value "220nF 16V")
      (footprint "eagle-import:C0805")
      (libsource (lib "eagle-import") (part "C-0805"))
    )
    (comp (ref "C23")
      (value "100uF 16V")
      (footprint "eagle-import:WCAP-PSHP_6.3X5.8(DXL)")
      (libsource (lib "eagle-import") (part "WCAP-PSHP_6.3X5.8_875115644009"))
    )
    (comp (ref "C35")
      (value "22uF 400V")
      (footprint "eagle-import:WCAP-HSAH_D6.3H7.7P2.2")
      (libsource (lib "eagle-import") (part "WCAP-HSAH_D6.3H7.7P2.2_875585745003"))
    )
    (comp (ref "C45")
      (value "1uF 50V")
      (footprint "eagle-import:C0805")
      (libsource (lib "eagle-import") (part "C-0805"))
    )
    (comp (ref "C46")
      (value "2.2uF 10V")
      (footprint "eagle-import:C0603")
      (libsource (lib "eagle-import") (part "C-0603"))
    )
    (comp (ref "C47")
      (value "22uF 400V")
      (footprint "eagle-import:WCAP-HSAH_D6.3H7.7P2.2")
      (libsource (lib "eagle-import") (part "WCAP-HSAH_D6.3H7.7P2.2_875585745003"))
    )
    (comp (ref "C51")
      (value "1nF 50V")
      (footprint "eagle-import:C0603")
      (libsource (lib "eagle-import") (part "C-0603"))
    )
    (comp (ref "C52")
      (value "220nF 16V")
      (footprint "eagle-import:C0805")
      (libsource (lib "eagle-import") (part "C-0805"))
    )
    (comp (ref "C53")
      (value "100uF 16V")
      (footprint "eagle-import:WCAP-PSHP_6.3X5.8(DXL)")
      (libsource (lib "eagle-import") (part "WCAP-PSHP_6.3X5.8_875115644009"))
    )
    (comp (ref "C57")
      (value "1uF 50V")
      (footprint "eagle-import:C0805")
      (libsource (lib "eagle-import") (part "C-0805"))
    )
    (comp (ref "D9")
      (value "1N4007")
      (footprint "eagle-import:SMA")
      (libsource (lib "eagle-import") (part "S1M"))
    )
    (comp (ref "D10")
      (value "1N4007")
      (footprint "eagle-import:SMA")
      (libsource (lib "eagle-import") (part "S1M"))
    )
    (comp (ref "D11")
      (value "US1J")
      (footprint "eagle-import:SMA")
      (libsource (lib "eagle-import") (part "S1M"))
    )
    (comp (ref "D12")
      (value "1N4007")
      (footprint "eagle-import:SMA")
      (libsource (lib "eagle-import") (part "S1M"))
    )
    (comp (ref "D13")
      (value "1N4007")
      (footprint "eagle-import:SMA")
      (libsource (lib "eagle-import") (part "S1M"))
    )
    (comp (ref "D14")
      (value "US1J")
      (footprint "eagle-import:SMA")
      (libsource (lib "eagle-import") (part "S1M"))
    )
    (comp (ref "FB-NI1")
      (value "TP")
      (footprint "eagle-import:TP")
      (libsource (lib "eagle-import") (part "TP"))
    )
    (comp (ref "FB-NI2")
      (value "TP")
      (footprint "eagle-import:TP")
      (libsource (lib "eagle-import") (part "TP"))
    )
    (comp (ref "GND") (value "TP") (footprint "eagle-import:TP") (libsource (lib "eagle-import") (part "TP")))
    (comp (ref "GND-3")
      (value "TP")
      (footprint "eagle-import:TP")
      (libsource (lib "eagle-import") (part "TP"))
    )
    (comp (ref "GND-5")
      (value "TP")
      (footprint "eagle-import:TP")
      (libsource (lib "eagle-import") (part "TP"))
    )
    (comp (ref "IC1")
      (value "MP2315GJ-Z")
      (footprint "eagle-import:SOT65P280X110-8N")
      (libsource (lib "eagle-import") (part "MP2315TSOT23-8"))
    )
    (comp (ref "IC2")
      (value "MP2315S")
      (footprint "eagle-import:SOT65P280X110-8N")
      (libsource (lib "eagle-import") (part "MP2315TSOT23-8"))
    )
    (comp (ref "IC5")
      (value "MP150GJ")
      (footprint "eagle-import:SOT23-5")
      (libsource (lib "eagle-import") (part "MP150GJ"))
    )
    (comp (ref "IC13")
      (value "MP150GJ")
      (footprint "eagle-import:SOT23-5")
      (libsource (lib "eagle-import") (part "MP150GJ"))
    )
    (comp (ref "J7") (value "JP") (footprint "eagle-import:SJ") (libsource (lib "eagle-import") (part "SJ")))
    (comp (ref "J8")
      (value "0R")
      (footprint "eagle-import:0805")
      (libsource (lib "eagle-import") (part "R0805"))
    )
    (comp (ref "J9")
      (value "0R")
      (footprint "eagle-import:0805")
      (libsource (lib "eagle-import") (part "R0805"))
    )
    (comp (ref "J10")
      (value "0R")
      (footprint "eagle-import:0805")
      (libsource (lib "eagle-import") (part "R0805"))
    )
    (comp (ref "L-REC1")
      (value "TP")
      (footprint "eagle-import:TP")
      (libsource (lib "eagle-import") (part "TP"))
    )
    (comp (ref "L-REC2")
      (value "TP")
      (footprint "eagle-import:TP")
      (libsource (lib "eagle-import") (part "TP"))
    )
    (comp (ref "L1")
      (value "4.9uH")
      (footprint "eagle-import:SRR5228A")
      (libsource (lib "eagle-import") (part "L"))
    )
    (comp (ref "L2")
      (value "4.2uH")
      (footprint "eagle-import:SRR5228A")
      (libsource (lib "eagle-import") (part "L"))
    )
    (comp (ref "L3")
      (value "FNR6028S102MT 1mH")
      (footprint "eagle-import:WE-HEPA_6030")
      (libsource (lib "eagle-import") (part "WE-HEPA_6030_78408063006"))
    )
    (comp (ref "L4")
      (value "FNR6028S102MT 1mH")
      (footprint "eagle-import:WE-HEPA_6030")
      (libsource (lib "eagle-import") (part "WE-HEPA_6030_78408063006"))
    )
    (comp (ref "L5")
      (value "FNR6028S102MT 1mH")
      (footprint "eagle-import:WE-HEPA_6030")
      (libsource (lib "eagle-import") (part "WE-HEPA_6030_78408063006"))
    )
    (comp (ref "L6")
      (value "FNR6028S102MT 1mH")
      (footprint "eagle-import:WE-HEPA_6030")
      (libsource (lib "eagle-import") (part "WE-HEPA_6030_78408063006"))
    )
    (comp (ref "R1")
      (value "499K")
      (footprint "eagle-import:0402")
      (libsource (lib "eagle-import") (part "R0402"))
    )
    (comp (ref "R2")
      (value "499K")
      (footprint "eagle-import:0402")
      (libsource (lib "eagle-import") (part "R0402"))
    )
    (comp (ref "R3")
      (value "100K")
      (footprint "eagle-import:0402")
      (libsource (lib "eagle-import") (part "R0402"))
    )
    (comp (ref "R4")
      (value "9.09K")
      (footprint "eagle-import:0402")
      (libsource (lib "eagle-import") (part "R0402"))
    )
    (comp (ref "R5")
      (value "100K")
      (footprint "eagle-import:0402")
      (libsource (lib "eagle-import") (part "R0402"))
    )
    (comp (ref "R6")
      (value "7.5K")
      (footprint "eagle-import:0402")
      (libsource (lib "eagle-import") (part "R0402"))
    )
    (comp (ref "R7")
      (value "10R")
      (footprint "eagle-import:0402")
      (libsource (lib "eagle-import") (part "R0402"))
    )
    (comp (ref "R8")
      (value "20K")
      (footprint "eagle-import:0402")
      (libsource (lib "eagle-import") (part "R0402"))
    )
    (comp (ref "R9")
      (value "10R")
      (footprint "eagle-import:0402")
      (libsource (lib "eagle-import") (part "R0402"))
    )
    (comp (ref "R10")
      (value "33K")
      (footprint "eagle-import:0402")
      (libsource (lib "eagle-import") (part "R0402"))
    )
    (comp (ref "R11")
      (value "40.2K")
      (footprint "eagle-import:0402")
      (libsource (lib "eagle-import") (part "R0402"))
    )
    (comp (ref "R12")
      (value "7.5K")
      (footprint "eagle-import:0402")
      (libsource (lib "eagle-import") (part "R0402"))
    )
    (comp (ref "R13")
      (value "40.2K")
      (footprint "eagle-import:0402")
      (libsource (lib "eagle-import") (part "R0402"))
    )
    (comp (ref "R14")
      (value "12.7K")
      (footprint "eagle-import:0402")
      (libsource (lib "eagle-import") (part "R0402"))
    )
    (comp (ref "R57") (value "JP") (footprint "eagle-import:SJ") (libsource (lib "eagle-import") (part "SJ")))
    (comp (ref "R58") (value "JP") (footprint "eagle-import:SJ") (libsource (lib "eagle-import") (part "SJ")))
    (comp (ref "R59") (value "JP") (footprint "eagle-import:SJ") (libsource (lib "eagle-import") (part "SJ")))
    (comp (ref "R60")
      (value "4.99K")
      (footprint "eagle-import:0603")
      (libsource (lib "eagle-import") (part "R0603"))
    )
    (comp (ref "R61")
      (value "4.99K")
      (footprint "eagle-import:0603")
      (libsource (lib "eagle-import") (part "R0603"))
    )
    (comp (ref "R62")
      (value "10R 1W")
      (footprint "eagle-import:2512")
      (libsource (lib "eagle-import") (part "R2512"))
    )
    (comp (ref "R94")
      (value "100K")
      (footprint "eagle-import:0402")
      (libsource (lib "eagle-import") (part "R0402"))
    )
    (comp (ref "R95")
      (value "10K")
      (footprint "eagle-import:0402")
      (libsource (lib "eagle-import") (part "R0402"))
    )
    (comp (ref "R96")
      (value "10K")
      (footprint "eagle-import:0805")
      (libsource (lib "eagle-import") (part "R0805"))
    )
    (comp (ref "R105")
      (value "4.99K")
      (footprint "eagle-import:0603")
      (libsource (lib "eagle-import") (part "R0603"))
    )
    (comp (ref "R106")
      (value "10R 1W")
      (footprint "eagle-import:2512")
      (libsource (lib "eagle-import") (part "R2512"))
    )
    (comp (ref "R107")
      (value "4.99K")
      (footprint "eagle-import:0603")
      (libsource (lib "eagle-import") (part "R0603"))
    )
    (comp (ref "R108")
      (value "10K")
      (footprint "eagle-import:0805")
      (libsource (lib "eagle-import") (part "R0805"))
    )
    (comp (ref "SW") (value "TP") (footprint "eagle-import:TP") (libsource (lib "eagle-import") (part "TP")))
    (comp (ref "SW3") (value "TP") (footprint "eagle-import:TP") (libsource (lib "eagle-import") (part "TP")))
    (comp (ref "VNI1")
      (value "TP")
      (footprint "eagle-import:TP")
      (libsource (lib "eagle-import") (part "TP"))
    )
    (comp (ref "VNI2")
      (value "TP")
      (footprint "eagle-import:TP")
      (libsource (lib "eagle-import") (part "TP"))
    )
    (comp (ref "Z1")
      (value "SMAJ15A")
      (footprint "eagle-import:SUPRESSOR_SMAJ")
      (libsource (lib "eagle-import") (part "SUPRESSOR_TVS-UD-SMAJ"))
    )
  )
  (nets
    (net (code "1") (name "+3V3") (class "Default")
      (node (ref "3VDC") (pin "TP") (pinfunction "P$1_TP") (pintype "bidirectional"))
      (node (ref "C12") (pin "1") (pinfunction "1_1") (pintype "passive"))
      (node (ref "C15") (pin "1") (pinfunction "1_1") (pintype "passive"))
      (node (ref "C18") (pin "1") (pinfunction "1_1") (pintype "passive"))
      (node (ref "C19") (pin "1") (pinfunction "1_1") (pintype "passive"))
      (node (ref "C20") (pin "1") (pinfunction "1_1") (pintype "passive"))
      (node (ref "C33") (pin "1") (pinfunction "1_1") (pintype "passive"))
      (node (ref "C34") (pin "1") (pinfunction "1_1") (pintype "passive"))
      (node (ref "IC4") (pin "5") (pinfunction "VDD_5") (pintype "bidirectional"))
      (node (ref "IC9") (pin "16") (pinfunction "VCC_16") (pintype "power_in"))
      (node (ref "J1") (pin "4") (pinfunction "4_4") (pintype "bidirectional"))
      (node (ref "J1") (pin "5") (pinfunction "5_5") (pintype "bidirectional"))
      (node (ref "J1") (pin "6") (pinfunction "6_6") (pintype "bidirectional"))
      (node (ref "L2") (pin "2") (pinfunction "2_2") (pintype "passive"))
      (node (ref "R13") (pin "1") (pinfunction "1_1") (pintype "passive"))
      (node (ref "R89") (pin "5") (pinfunction "5_5") (pintype "passive"))
      (node (ref "R89") (pin "6") (pinfunction "6_6") (pintype "passive"))
      (node (ref "R89") (pin "7") (pinfunction "7_7") (pintype "passive"))
      (node (ref "R89") (pin "8") (pinfunction "8_8") (pintype "passive"))
      (node (ref "R90") (pin "5") (pinfunction "5_5") (pintype "passive"))
      (node (ref "R90") (pin "6") (pinfunction "6_6") (pintype "passive"))
      (node (ref "R90") (pin "7") (pinfunction "7_7") (pintype "passive"))
      (node (ref "R90") (pin "8") (pinfunction "8_8") (pintype "passive"))
      (node (ref "R93") (pin "5") (pinfunction "5_5") (pintype "passive"))
      (node (ref "R93") (pin "6") (pinfunction "6_6") (pintype "passive"))
      (node (ref "R93") (pin "7") (pinfunction "7_7") (pintype "passive"))
      (node (ref "R93") (pin "8") (pinfunction "8_8") (pintype "passive"))
    )
    (net (code "2") (name "+5V") (class "Default")
      (node (ref "5VDC") (pin "TP") (pinfunction "P$1_TP") (pintype "bidirectional"))
      (node (ref "C11") (pin "1") (pinfunction "1_1") (pintype "passive"))
      (node (ref "C14") (pin "1") (pinfunction "1_1") (pintype "passive"))
      (node (ref "C17") (pin "1") (pinfunction "1_1") (pintype "passive"))
      (node (ref "J1") (pin "1") (pinfunction "1_1") (pintype "bidirectional"))
      (node (ref "J1") (pin "2") (pinfunction "2_2") (pintype "bidirectional"))
      (node (ref "J1") (pin "3") (pinfunction "3_3") (pintype "bidirectional"))
      (node (ref "L1") (pin "2") (pinfunction "2_2") (pintype "passive"))
      (node (ref "R11") (pin "1") (pinfunction "1_1") (pintype "passive"))
    )
    (net (code "3") (name "+5V_MEA_G1") (class "Default")
      (node (ref "5V-NI1") (pin "TP") (pinfunction "P$1_TP") (pintype "bidirectional"))
      (node (ref "C23") (pin "1") (pinfunction "+_1") (pintype "passive"))
      (node (ref "C45") (pin "2") (pinfunction "2_2") (pintype "passive"))
      (node (ref "D9") (pin "A") (pinfunction "A_A") (pintype "passive"))
      (node (ref "IC10") (pin "1") (pinfunction "VDD_1") (pintype "power_in"))
      (node (ref "IC12") (pin "1") (pinfunction "VDD_1") (pintype "power_in"))
      (node (ref "IC6") (pin "1") (pinfunction "VDD_1") (pintype "power_in"))
      (node (ref "IC8") (pin "1") (pinfunction "VDD_1") (pintype "power_in"))
      (node (ref "J7") (pin "1") (pinfunction "1_1") (pintype "passive"))
      (node (ref "L3") (pin "2") (pinfunction "2_2") (pintype "passive"))
      (node (ref "R63") (pin "1") (pinfunction "1_1") (pintype "passive"))
      (node (ref "R63") (pin "2") (pinfunction "2_2") (pintype "passive"))
      (node (ref "R63") (pin "3") (pinfunction "3_3") (pintype "passive"))
      (node (ref "R63") (pin "4") (pinfunction "4_4") (pintype "passive"))
      (node (ref "R96") (pin "1") (pinfunction "1_1") (pintype "passive"))
    )
    (net (code "4") (name "+5V_MEA_G2") (class "Default")
      (node (ref "5V-NI2") (pin "TP") (pinfunction "P$1_TP") (pintype "bidirectional"))
      (node (ref "C53") (pin "1") (pinfunction "+_1") (pintype "passive"))
      (node (ref "C57") (pin "2") (pinfunction "2_2") (pintype "passive"))
      (node (ref "D13") (pin "A") (pinfunction "A_A") (pintype "passive"))
      (node (ref "IC11") (pin "1") (pinfunction "VDD_1") (pintype "power_in"))
      (node (ref "IC14") (pin "1") (pinfunction "VDD_1") (pintype "power_in"))
      (node (ref "IC16") (pin "1") (pinfunction "VDD_1") (pintype "power_in"))
      (node (ref "IC7") (pin "1") (pinfunction "VDD_1") (pintype "power_in"))
      (node (ref "J7") (pin "2") (pinfunction "2_2") (pintype "passive"))
      (node (ref "L5") (pin "2") (pinfunction "2_2") (pintype "passive"))
      (node (ref "R108") (pin "1") (pinfunction "1_1") (pintype "passive"))
      (node (ref "R110") (pin "1") (pinfunction "1_1") (pintype "passive"))
      (node (ref "R110") (pin "2") (pinfunction "2_2") (pintype "passive"))
      (node (ref "R110") (pin "3") (pinfunction "3_3") (pintype "passive"))
      (node (ref "R110") (pin "4") (pinfunction "4_4") (pintype "passive"))
      (node (ref "R64") (pin "1") (pinfunction "1_1") (pintype "passive"))
      (node (ref "R64") (pin "2") (pinfunction "2_2") (pintype "passive"))
      (node (ref "R64") (pin "3") (pinfunction "3_3") (pintype "passive"))
      (node (ref "R64") (pin "4") (pinfunction "4_4") (pintype "passive"))
    )
    (net (code "5") (name "+12V") (class "Default")
      (node (ref "C1") (pin "1") (pinfunction "1_1") (pintype "passive"))
      (node (ref "C2") (pin "1") (pinfunction "1_1") (pintype "passive"))
      (node (ref "C3") (pin "1") (pinfunction "1_1") (pintype "passive"))
      (node (ref "C4") (pin "1") (pinfunction "1_1") (pintype "passive"))
      (node (ref "D1") (pin "C") (pinfunction "C_C") (pintype "passive"))
      (node (ref "D2") (pin "C") (pinfunction "C_C") (pintype "passive"))
      (node (ref "D3") (pin "C") (pinfunction "C_C") (pintype "passive"))
      (node (ref "D4") (pin "C") (pinfunction "C_C") (pintype "passive"))
      (node (ref "D5") (pin "C") (pinfunction "C_C") (pintype "passive"))
      (node (ref "D6") (pin "C") (pinfunction "C_C") (pintype "passive"))
      (node (ref "D7") (pin "C") (pinfunction "C_C") (pintype "passive"))
      (node (ref "D8") (pin "C") (pinfunction "C_C") (pintype "passive"))
      (node (ref "IC1") (pin "2") (pinfunction "IN_2") (pintype "bidirectional"))
      (node (ref "IC2") (pin "2") (pinfunction "IN_2") (pintype "bidirectional"))
      (node (ref "IC3") (pin "10") (pinfunction "COM_10") (pintype "bidirectional"))
      (node (ref "J10") (pin "1") (pinfunction "1_1") (pintype "passive"))
      (node (ref "J8") (pin "1") (pinfunction "1_1") (pintype "passive"))
      (node (ref "J9") (pin "1") (pinfunction "1_1") (pintype "passive"))
      (node (ref "K1") (pin "8") (pinfunction "8_8") (pintype "passive"))
      (node (ref "K2") (pin "8") (pinfunction "8_8") (pintype "passive"))
      (node (ref "K3") (pin "8") (pinfunction "8_8") (pintype "passive"))
      (node (ref "K4") (pin "8") (pinfunction "8_8") (pintype "passive"))
      (node (ref "K5") (pin "8") (pinfunction "8_8") (pintype "passive"))
      (node (ref "K6") (pin "8") (pinfunction "8_8") (pintype "passive"))
      (node (ref "K7") (pin "8") (pinfunction "8_8") (pintype "passive"))
      (node (ref "K8") (pin "8") (pinfunction "8_8") (pintype "passive"))
      (node (ref "R1") (pin "1") (pinfunction "1_1") (pintype "passive"))
      (node (ref "R2") (pin "1") (pinfunction "1_1") (pintype "passive"))
      (node (ref "R94") (pin "2") (pinfunction "2_2") (pintype "passive"))
    )
    (net (code "6") (name "+12V_MEA") (class "Default")
      (node (ref "J1") (pin "13") (pinfunction "13_13") (pintype "bidirectional"))
      (node (ref "R94") (pin "1") (pinfunction "1_1") (pintype "passive"))
      (node (ref "R95") (pin "2") (pinfunction "2_2") (pintype "passive"))
    )
    (net (code "7") (name "AC_L") (class "Default")
      (node (ref "AC/DC1") (pin "AC_L") (pinfunction "AC/L_AC_L") (pintype "input"))
      (node (ref "AC/DC2") (pin "AC/L") (pinfunction "AC/L_AC/L") (pintype "input"))
      (node (ref "AC_L") (pin "1") (pinfunction "KL_1") (pintype "passive"))
      (node (ref "AC_L") (pin "2") (pinfunction "KL_2") (pintype "passive"))
      (node (ref "K1") (pin "3") (pinfunction "3_3") (pintype "passive"))
      (node (ref "K1") (pin "6") (pinfunction "6_6") (pintype "passive"))
      (node (ref "K2") (pin "3") (pinfunction "3_3") (pintype "passive"))
      (node (ref "K2") (pin "6") (pinfunction "6_6") (pintype "passive"))
      (node (ref "K3") (pin "3") (pinfunction "3_3") (pintype "passive"))
      (node (ref "K3") (pin "6") (pinfunction "6_6") (pintype "passive"))
      (node (ref "K4") (pin "3") (pinfunction "3_3") (pintype "passive"))
      (node (ref "K4") (pin "6") (pinfunction "6_6") (pintype "passive"))
      (node (ref "K5") (pin "3") (pinfunction "3_3") (pintype "passive"))
      (node (ref "K5") (pin "6") (pinfunction "6_6") (pintype "passive"))
      (node (ref "K6") (pin "3") (pinfunction "3_3") (pintype "passive"))
      (node (ref "K6") (pin "6") (pinfunction "6_6") (pintype "passive"))
      (node (ref "K7") (pin "3") (pinfunction "3_3") (pintype "passive"))
      (node (ref "K7") (pin "6") (pinfunction "6_6") (pintype "passive"))
      (node (ref "K8") (pin "3") (pinfunction "3_3") (pintype "passive"))
      (node (ref "K8") (pin "6") (pinfunction "6_6") (pintype "passive"))
      (node (ref "R106") (pin "1") (pinfunction "1_1") (pintype "passive"))
      (node (ref "R62") (pin "1") (pinfunction "1_1") (pintype "passive"))
    )
    (net (code "8") (name "AC_N") (class "Default")
      (node (ref "AC/DC1") (pin "AC_N") (pinfunction "AC/N_AC_N") (pintype "input"))
      (node (ref "AC/DC2") (pin "AC/N") (pinfunction "AC/N_AC/N") (pintype "input"))
      (node (ref "AC_N") (pin "1") (pinfunction "KL_1") (pintype "passive"))
      (node (ref "AC_N") (pin "2") (pinfunction "KL_2") (pintype "passive"))
      (node (ref "R57") (pin "1") (pinfunction "1_1") (pintype "passive"))
      (node (ref "R58") (pin "1") (pinfunction "1_1") (pintype "passive"))
      (node (ref "R59") (pin "1") (pinfunction "1_1") (pintype "passive"))
    )
    (net (code "9") (name "AGND") (class "Default")
      (node (ref "C23") (pin "2") (pinfunction "-_2") (pintype "passive"))
      (node (ref "C24") (pin "2") (pinfunction "2_2") (pintype "passive"))
      (node (ref "C25") (pin "2") (pinfunction "2_2") (pintype "passive"))
      (node (ref "C26") (pin "2") (pinfunction "2_2") (pintype "passive"))
      (node (ref "C27") (pin "2") (pinfunction "2_2") (pintype "passive"))
      (node (ref "C28") (pin "2") (pinfunction "2_2") (pintype "passive"))
      (node (ref "C29") (pin "2") (pinfunction "2_2") (pintype "passive"))
      (node (ref "C30") (pin "2") (pinfunction "2_2") (pintype "passive"))
      (node (ref "C31") (pin "2") (pinfunction "2_2") (pintype "passive"))
      (node (ref "C32") (pin "2") (pinfunction "2_2") (pintype "passive"))
      (node (ref "C35") (pin "1") (pinfunction "-_1") (pintype "passive"))
      (node (ref "C36") (pin "2") (pinfunction "2_2") (pintype "passive"))
      (node (ref "C37") (pin "2") (pinfunction "2_2") (pintype "passive"))
      (node (ref "C38") (pin "2") (pinfunction "2_2") (pintype "passive"))
      (node (ref "C39") (pin "2") (pinfunction "2_2") (pintype "passive"))
      (node (ref "C40") (pin "2") (pinfunction "2_2") (pintype "passive"))
      (node (ref "C41") (pin "2") (pinfunction "2_2") (pintype "passive"))
      (node (ref "C42") (pin "2") (pinfunction "2_2") (pintype "passive"))
      (node (ref "C43") (pin "2") (pinfunction "2_2") (pintype "passive"))
      (node (ref "C44") (pin "2") (pinfunction "2_2") (pintype "passive"))
      (node (ref "C45") (pin "1") (pinfunction "1_1") (pintype "passive"))
      (node (ref "C47") (pin "1") (pinfunction "-_1") (pintype "passive"))
      (node (ref "C48") (pin "2") (pinfunction "2_2") (pintype "passive"))
      (node (ref "C49") (pin "2") (pinfunction "2_2") (pintype "passive"))
      (node (ref "C50") (pin "2") (pinfunction "2_2") (pintype "passive"))
      (node (ref "C53") (pin "2") (pinfunction "-_2") (pintype "passive"))
      (node (ref "C54") (pin "2") (pinfunction "2_2") (pintype "passive"))
      (node (ref "C55") (pin "2") (pinfunction "2_2") (pintype "passive"))
      (node (ref "C56") (pin "2") (pinfunction "2_2") (pintype "passive"))
      (node (ref "C57") (pin "1") (pinfunction "1_1") (pintype "passive"))
      (node (ref "D11") (pin "A") (pinfunction "A_A") (pintype "passive"))
      (node (ref "D14") (pin "A") (pinfunction "A_A") (pintype "passive"))
      (node (ref "IC10") (pin "5") (pinfunction "GND_5") (pintype "power_in"))
      (node (ref "IC11") (pin "5") (pinfunction "GND_5") (pintype "power_in"))
      (node (ref "IC12") (pin "5") (pinfunction "GND_5") (pintype "power_in"))
      (node (ref "IC14") (pin "5") (pinfunction "GND_5") (pintype "power_in"))
      (node (ref "IC16") (pin "5") (pinfunction "GND_5") (pintype "power_in"))
      (node (ref "IC6") (pin "5") (pinfunction "GND_5") (pintype "power_in"))
      (node (ref "IC7") (pin "5") (pinfunction "GND_5") (pintype "power_in"))
      (node (ref "IC8") (pin "5") (pinfunction "GND_5") (pintype "power_in"))
      (node (ref "R104") (pin "2") (pinfunction "2_2") (pintype "passive"))
      (node (ref "R108") (pin "2") (pinfunction "2_2") (pintype "passive"))
      (node (ref "R120") (pin "2") (pinfunction "2_2") (pintype "passive"))
      (node (ref "R40") (pin "2") (pinfunction "2_2") (pintype "passive"))
      (node (ref "R48") (pin "2") (pinfunction "2_2") (pintype "passive"))
      (node (ref "R56") (pin "2") (pinfunction "2_2") (pintype "passive"))
      (node (ref "R57") (pin "2") (pinfunction "2_2") (pintype "passive"))
      (node (ref "R58") (pin "2") (pinfunction "2_2") (pintype "passive"))
      (node (ref "R59") (pin "2") (pinfunction "2_2") (pintype "passive"))
      (node (ref "R72") (pin "2") (pinfunction "2_2") (pintype "passive"))
      (node (ref "R80") (pin "2") (pinfunction "2_2") (pintype "passive"))
      (node (ref "R88") (pin "2") (pinfunction "2_2") (pintype "passive"))
      (node (ref "R96") (pin "2") (pinfunction "2_2") (pintype "passive"))
    )
    (net (code "10") (name "C13_IN1") (class "Default")
      (node (ref "R25") (pin "2") (pinfunction "2_2") (pintype "passive"))
      (node (ref "R33") (pin "1") (pinfunction "1_1") (pintype "passive"))
      (node (ref "R35") (pin "2") (pinfunction "2_2") (pintype "passive"))
    )
    (net (code "11") (name "C13_IN2") (class "Default")
      (node (ref "R32") (pin "2") (pinfunction "2_2") (pintype "passive"))
      (node (ref "R49") (pin "1") (pinfunction "1_1") (pintype "passive"))
      (node (ref "R51") (pin "2") (pinfunction "2_2") (pintype "passive"))
    )
    (net (code "12") (name "C13_IN3") (class "Default")
      (node (ref "R31") (pin "2") (pinfunction "2_2") (pintype "passive"))
      (node (ref "R65") (pin "1") (pinfunction "1_1") (pintype "passive"))
      (node (ref "R67") (pin "2") (pinfunction "2_2") (pintype "passive"))
    )
    (net (code "13") (name "C13_IN4") (class "Default")
      (node (ref "R30") (pin "2") (pinfunction "2_2") (pintype "passive"))
      (node (ref "R81") (pin "1") (pinfunction "1_1") (pintype "passive"))
      (node (ref "R83") (pin "2") (pinfunction "2_2") (pintype "passive"))
    )
    (net (code "14") (name "C13_IN5") (class "Default")
      (node (ref "R26") (pin "2") (pinfunction "2_2") (pintype "passive"))
      (node (ref "R41") (pin "1") (pinfunction "1_1") (pintype "passive"))
      (node (ref "R43") (pin "2") (pinfunction "2_2") (pintype "passive"))
    )
    (net (code "15") (name "C13_IN6") (class "Default")
      (node (ref "R27") (pin "2") (pinfunction "2_2") (pintype "passive"))
      (node (ref "R73") (pin "1") (pinfunction "1_1") (pintype "passive"))
      (node (ref "R75") (pin "2") (pinfunction "2_2") (pintype "passive"))
    )
    (net (code "16") (name "C13_IN7") (class "Default")
      (node (ref "R28") (pin "2") (pinfunction "2_2") (pintype "passive"))
      (node (ref "R97") (pin "1") (pinfunction "1_1") (pintype "passive"))
      (node (ref "R99") (pin "2") (pinfunction "2_2") (pintype "passive"))
    )
    (net (code "17") (name "C13_IN8") (class "Default")
      (node (ref "R113") (pin "1") (pinfunction "1_1") (pintype "passive"))
      (node (ref "R115") (pin "2") (pinfunction "2_2") (pintype "passive"))
      (node (ref "R29") (pin "2") (pinfunction "2_2") (pintype "passive"))
    )
    (net (code "18") (name "GND") (class "Default")
      (node (ref "AC/DC1") (pin "-V") (pinfunction "-V_-V") (pintype "output"))
      (node (ref "AC/DC2") (pin "-V") (pinfunction "-V_-V") (pintype "output"))
      (node (ref "C1") (pin "2") (pinfunction "2_2") (pintype "passive"))
      (node (ref "C10") (pin "2") (pinfunction "2_2") (pintype "passive"))
      (node (ref "C13") (pin "2") (pinfunction "2_2") (pintype "passive"))
      (node (ref "C14") (pin "2") (pinfunction "2_2") (pintype "passive"))
      (node (ref "C15") (pin "2") (pinfunction "2_2") (pintype "passive"))
      (node (ref "C16") (pin "2") (pinfunction "2_2") (pintype "passive"))
      (node (ref "C17") (pin "2") (pinfunction "2_2") (pintype "passive"))
      (node (ref "C18") (pin "2") (pinfunction "2_2") (pintype "passive"))
      (node (ref "C19") (pin "2") (pinfunction "2_2") (pintype "passive"))
      (node (ref "C2") (pin "2") (pinfunction "2_2") (pintype "passive"))
      (node (ref "C20") (pin "2") (pinfunction "2_2") (pintype "passive"))
      (node (ref "C3") (pin "2") (pinfunction "2_2") (pintype "passive"))
      (node (ref "C33") (pin "2") (pinfunction "2_2") (pintype "passive"))
      (node (ref "C34") (pin "2") (pinfunction "2_2") (pintype "passive"))
      (node (ref "C4") (pin "2") (pinfunction "2_2") (pintype "passive"))
      (node (ref "C6") (pin "2") (pinfunction "2_2") (pintype "passive"))
      (node (ref "C7") (pin "2") (pinfunction "2_2") (pintype "passive"))
      (node (ref "GND") (pin "TP") (pinfunction "P$1_TP") (pintype "bidirectional"))
      (node (ref "GND-3") (pin "TP") (pinfunction "P$1_TP") (pintype "bidirectional"))
      (node (ref "GND-5") (pin "TP") (pinfunction "P$1_TP") (pintype "bidirectional"))
      (node (ref "IC1") (pin "4") (pinfunction "GND_4") (pintype "bidirectional"))
      (node (ref "IC2") (pin "4") (pinfunction "GND_4") (pintype "bidirectional"))
      (node (ref "IC3") (pin "9") (pinfunction "GND_9") (pintype "bidirectional"))
      (node (ref "IC4") (pin "11") (pinfunction "A0_11") (pintype "bidirectional"))
      (node (ref "IC4") (pin "12") (pinfunction "A1_12") (pintype "bidirectional"))
      (node (ref "IC4") (pin "13") (pinfunction "A2_13") (pintype "bidirectional"))
      (node (ref "IC4") (pin "6") (pinfunction "VSS_6") (pintype "bidirectional"))
      (node (ref "IC4") (pin "PAD") (pinfunction "VSS_PAD") (pintype "bidirectional"))
      (node (ref "IC9") (pin "8") (pinfunction "GND_8") (pintype "power_in"))
      (node (ref "J1") (pin "12") (pinfunction "12_12") (pintype "bidirectional"))
      (node (ref "J1") (pin "14") (pinfunction "14_14") (pintype "bidirectional"))
      (node (ref "J1") (pin "16") (pinfunction "16_16") (pintype "bidirectional"))
      (node (ref "J1") (pin "9") (pinfunction "9_9") (pintype "bidirectional"))
      (node (ref "J1") (pin "Z0") (pinfunction "Z1_Z0") (pintype "bidirectional"))
      (node (ref "J1") (pin "Z1") (pinfunction "Z1_Z1") (pintype "bidirectional"))
      (node (ref "J1") (pin "Z2") (pinfunction "Z2_Z2") (pintype "bidirectional"))
      (node (ref "J1") (pin "Z3") (pinfunction "Z3_Z3") (pintype "bidirectional"))
      (node (ref "J1") (pin "Z4") (pinfunction "Z3_Z4") (pintype "bidirectional"))
      (node (ref "J1") (pin "Z5") (pinfunction "Z4_Z5") (pintype "bidirectional"))
      (node (ref "OPT1") (pin "11") (pinfunction "11_11") (pintype "passive"))
      (node (ref "OPT1") (pin "13") (pinfunction "13_13") (pintype "passive"))
      (node (ref "OPT1") (pin "15") (pinfunction "15_15") (pintype "passive"))
      (node (ref "OPT1") (pin "9") (pinfunction "9_9") (pintype "passive"))
      (node (ref "OPT2") (pin "5") (pinfunction "5_5") (pintype "passive"))
      (node (ref "OPT2") (pin "7") (pinfunction "7_7") (pintype "passive"))
      (node (ref "OPT3") (pin "5") (pinfunction "5_5") (pintype "passive"))
      (node (ref "OPT3") (pin "7") (pinfunction "7_7") (pintype "passive"))
      (node (ref "R12") (pin "2") (pinfunction "2_2") (pintype "passive"))
      (node (ref "R14") (pin "2") (pinfunction "2_2") (pintype "passive"))
      (node (ref "R4") (pin "2") (pinfunction "2_2") (pintype "passive"))
      (node (ref "R6") (pin "2") (pinfunction "2_2") (pintype "passive"))
      (node (ref "R95") (pin "1") (pinfunction "1_1") (pintype "passive"))
      (node (ref "Z1") (pin "A") (pinfunction "A_A") (pintype "passive"))
    )
    (net (code "19") (name "I2C_SCL") (class "Default")
      (node (ref "IC4") (pin "8") (pinfunction "SCL_8") (pintype "bidirectional"))
      (node (ref "J1") (pin "8") (pinfunction "8_8") (pintype "bidirectional"))
    )
    (net (code "20") (name "I2C_SDA") (class "Default")
      (node (ref "IC4") (pin "9") (pinfunction "SDA_9") (pintype "bidirectional"))
      (node (ref "J1") (pin "7") (pinfunction "7_7") (pintype "bidirectional"))
    )
    (net (code "21") (name "MCP_REL_RST") (class "Default")
      (node (ref "IC4") (pin "14") (pinfunction "~{RESET}_14") (pintype "bidirectional"))
      (node (ref "J1") (pin "15") (pinfunction "15_15") (pintype "bidirectional"))
    )
    (net (code "22") (name "MUX_A") (class "Default")
      (node (ref "IC4") (pin "25") (pinfunction "IO2.0_25") (pintype "bidirectional"))
      (node (ref "IC9") (pin "11") (pinfunction "A_11") (pintype "input"))
      (node (ref "R93") (pin "4") (pinfunction "4_4") (pintype "passive"))
    )
    (net (code "23") (name "MUX_B") (class "Default")
      (node (ref "IC4") (pin "26") (pinfunction "IO2.1_26") (pintype "bidirectional"))
      (node (ref "IC9") (pin "10") (pinfunction "B_10") (pintype "input"))
      (node (ref "R93") (pin "3") (pinfunction "3_3") (pintype "passive"))
    )
    (net (code "24") (name "MUX_C") (class "Default")
      (node (ref "IC4") (pin "27") (pinfunction "IO2.2_27") (pintype "bidirectional"))
      (node (ref "IC9") (pin "9") (pinfunction "C_9") (pintype "input"))
      (node (ref "R93") (pin "2") (pinfunction "2_2") (pintype "passive"))
    )
    (net (code "25") (name "MUX_EN") (class "Default")
      (node (ref "IC4") (pin "28") (pinfunction "IO2.3_28") (pintype "bidirectional"))
      (node (ref "IC9") (pin "7") (pinfunction "~{EN}_7") (pintype "input"))
      (node (ref "R93") (pin "1") (pinfunction "1_1") (pintype "passive"))
    )
    (net (code "26") (name "Net-(3VFB-P$1)") (class "Default")
      (node (ref "3VFB") (pin "TP") (pinfunction "P$1_TP") (pintype "bidirectional"))
      (node (ref "C12") (pin "2") (pinfunction "2_2") (pintype "passive"))
      (node (ref "R10") (pin "2") (pinfunction "2_2") (pintype "passive"))
      (node (ref "R13") (pin "2") (pinfunction "2_2") (pintype "passive"))
      (node (ref "R14") (pin "1") (pinfunction "1_1") (pintype "passive"))
    )
    (net (code "27") (name "Net-(5VFB-P$1)") (class "Default")
      (node (ref "5VFB") (pin "TP") (pinfunction "P$1_TP") (pintype "bidirectional"))
      (node (ref "C11") (pin "2") (pinfunction "2_2") (pintype "passive"))
      (node (ref "R11") (pin "2") (pinfunction "2_2") (pintype "passive"))
      (node (ref "R12") (pin "1") (pinfunction "1_1") (pintype "passive"))
      (node (ref "R8") (pin "2") (pinfunction "2_2") (pintype "passive"))
    )
    (net (code "28") (name "Net-(12VDC-P$1)") (class "Default")
      (node (ref "12VDC") (pin "TP") (pinfunction "P$1_TP") (pintype "bidirectional"))
      (node (ref "AC/DC1") (pin "+V") (pinfunction "+V_+V") (pintype "output"))
      (node (ref "AC/DC2") (pin "+V") (pinfunction "+V_+V") (pintype "output"))
      (node (ref "C10") (pin "1") (pinfunction "1_1") (pintype "passive"))
      (node (ref "C13") (pin "1") (pinfunction "1_1") (pintype "passive"))
      (node (ref "C16") (pin "1") (pinfunction "1_1") (pintype "passive"))
      (node (ref "J10") (pin "2") (pinfunction "2_2") (pintype "passive"))
      (node (ref "J8") (pin "2") (pinfunction "2_2") (pintype "passive"))
      (node (ref "J9") (pin "2") (pinfunction "2_2") (pintype "passive"))
      (node (ref "Z1") (pin "C") (pinfunction "C_C") (pintype "passive"))
    )
    (net (code "29") (name "Net-(C8-Pad1)") (class "Default")
      (node (ref "C8") (pin "1") (pinfunction "1_1") (pintype "passive"))
      (node (ref "R7") (pin "1") (pinfunction "1_1") (pintype "passive"))
    )
    (net (code "30") (name "Net-(C9-Pad1)") (class "Default")
      (node (ref "C9") (pin "1") (pinfunction "1_1") (pintype "passive"))
      (node (ref "R9") (pin "1") (pinfunction "1_1") (pintype "passive"))
    )
    (net (code "31") (name "Net-(C22-Pad2)") (class "Default")
      (node (ref "C22") (pin "2") (pinfunction "2_2") (pintype "passive"))
      (node (ref "D9") (pin "C") (pinfunction "C_C") (pintype "passive"))
      (node (ref "R61") (pin "1") (pinfunction "1_1") (pintype "passive"))
    )
    (net (code "32") (name "Net-(C35-+)") (class "Default")
      (node (ref "C35") (pin "2") (pinfunction "+_2") (pintype "passive"))
      (node (ref "D10") (pin "C") (pinfunction "C_C") (pintype "passive"))
      (node (ref "L-REC1") (pin "TP") (pinfunction "P$1_TP") (pintype "bidirectional"))
      (node (ref "L4") (pin "1") (pinfunction "1_1") (pintype "passive"))
    )
    (net (code "33") (name "Net-(C47-+)") (class "Default")
      (node (ref "C47") (pin "2") (pinfunction "+_2") (pintype "passive"))
      (node (ref "D12") (pin "C") (pinfunction "C_C") (pintype "passive"))
      (node (ref "L-REC2") (pin "TP") (pinfunction "P$1_TP") (pintype "bidirectional"))
      (node (ref "L6") (pin "1") (pinfunction "1_1") (pintype "passive"))
    )
    (net (code "34") (name "Net-(C52-Pad2)") (class "Default")
      (node (ref "C52") (pin "2") (pinfunction "2_2") (pintype "passive"))
      (node (ref "D13") (pin "C") (pinfunction "C_C") (pintype "passive"))
      (node (ref "R105") (pin "1") (pinfunction "1_1") (pintype "passive"))
    )
    (net (code "35") (name "Net-(D10-PadA)") (class "Default")
      (node (ref "D10") (pin "A") (pinfunction "A_A") (pintype "passive"))
      (node (ref "R62") (pin "2") (pinfunction "2_2") (pintype "passive"))
    )
    (net (code "36") (name "Net-(D12-PadA)") (class "Default")
      (node (ref "D12") (pin "A") (pinfunction "A_A") (pintype "passive"))
      (node (ref "R106") (pin "2") (pinfunction "2_2") (pintype "passive"))
    )
    (net (code "37") (name "Net-(FB-NI1-P$1)") (class "Default")
      (node (ref "C5") (pin "2") (pinfunction "2_2") (pintype "passive"))
      (node (ref "FB-NI1") (pin "TP") (pinfunction "P$1_TP") (pintype "bidirectional"))
      (node (ref "IC13") (pin "2") (pinfunction "FB_2") (pintype "input"))
      (node (ref "R60") (pin "1") (pinfunction "1_1") (pintype "passive"))
      (node (ref "R61") (pin "2") (pinfunction "2_2") (pintype "passive"))
    )
    (net (code "38") (name "Net-(FB-NI2-P$1)") (class "Default")
      (node (ref "C51") (pin "2") (pinfunction "2_2") (pintype "passive"))
      (node (ref "FB-NI2") (pin "TP") (pinfunction "P$1_TP") (pintype "bidirectional"))
      (node (ref "IC5") (pin "2") (pinfunction "FB_2") (pintype "input"))
      (node (ref "R105") (pin "2") (pinfunction "2_2") (pintype "passive"))
      (node (ref "R107") (pin "1") (pinfunction "1_1") (pintype "passive"))
    )
    (net (code "39") (name "Net-(IC1-AAM)") (class "Default")
      (node (ref "IC1") (pin "1") (pinfunction "AAM_1") (pintype "bidirectional"))
      (node (ref "R3") (pin "2") (pinfunction "2_2") (pintype "passive"))
      (node (ref "R4") (pin "1") (pinfunction "1_1") (pintype "passive"))
    )
    (net (code "40") (name "Net-(IC1-BST)") (class "Default")
      (node (ref "IC1") (pin "5") (pinfunction "BST_5") (pintype "bidirectional"))
      (node (ref "R7") (pin "2") (pinfunction "2_2") (pintype "passive"))
    )
    (net (code "41") (name "Net-(IC1-EN)") (class "Default")
      (node (ref "IC1") (pin "6") (pinfunction "EN_6") (pintype "bidirectional"))
      (node (ref "R1") (pin "2") (pinfunction "2_2") (pintype "passive"))
    )
    (net (code "42") (name "Net-(IC1-FB)") (class "Default")
      (node (ref "IC1") (pin "8") (pinfunction "FB_8") (pintype "bidirectional"))
      (node (ref "R8") (pin "1") (pinfunction "1_1") (pintype "passive"))
    )
    (net (code "43") (name "Net-(IC1-SW)") (class "Default")
      (node (ref "C8") (pin "2") (pinfunction "2_2") (pintype "passive"))
      (node (ref "IC1") (pin "3") (pinfunction "SW_3") (pintype "bidirectional"))
      (node (ref "L1") (pin "1") (pinfunction "1_1") (pintype "passive"))
      (node (ref "SW") (pin "TP") (pinfunction "P$1_TP") (pintype "bidirectional"))
    )
    (net (code "44") (name "Net-(IC1-VCC)") (class "Default")
      (node (ref "C6") (pin "1") (pinfunction "1_1") (pintype "passive"))
      (node (ref "IC1") (pin "7") (pinfunction "VCC_7") (pintype "bidirectional"))
      (node (ref "R3") (pin "1") (pinfunction "1_1") (pintype "passive"))
    )
    (net (code "45") (name "Net-(IC2-AAM)") (class "Default")
      (node (ref "IC2") (pin "1") (pinfunction "AAM_1") (pintype "bidirectional"))
      (node (ref "R5") (pin "2") (pinfunction "2_2") (pintype "passive"))
      (node (ref "R6") (pin "1") (pinfunction "1_1") (pintype "passive"))
    )
    (net (code "46") (name "Net-(IC2-BST)") (class "Default")
      (node (ref "IC2") (pin "5") (pinfunction "BST_5") (pintype "bidirectional"))
      (node (ref "R9") (pin "2") (pinfunction "2_2") (pintype "passive"))
    )
    (net (code "47") (name "Net-(IC2-EN)") (class "Default")
      (node (ref "IC2") (pin "6") (pinfunction "EN_6") (pintype "bidirectional"))
      (node (ref "R2") (pin "2") (pinfunction "2_2") (pintype "passive"))
    )
    (net (code "48") (name "Net-(IC2-FB)") (class "Default")
      (node (ref "IC2") (pin "8") (pinfunction "FB_8") (pintype "bidirectional"))
      (node (ref "R10") (pin "1") (pinfunction "1_1") (pintype "passive"))
    )
    (net (code "49") (name "Net-(IC2-SW)") (class "Default")
      (node (ref "C9") (pin "2") (pinfunction "2_2") (pintype "passive"))
      (node (ref "IC2") (pin "3") (pinfunction "SW_3") (pintype "bidirectional"))
      (node (ref "L2") (pin "1") (pinfunction "1_1") (pintype "passive"))
      (node (ref "SW3") (pin "TP") (pinfunction "P$1_TP") (pintype "bidirectional"))
    )
    (net (code "50") (name "Net-(IC2-VCC)") (class "Default")
      (node (ref "C7") (pin "1") (pinfunction "1_1") (pintype "passive"))
      (node (ref "IC2") (pin "7") (pinfunction "VCC_7") (pintype "bidirectional"))
      (node (ref "R5") (pin "1") (pinfunction "1_1") (pintype "passive"))
    )
    (net (code "51") (name "Net-(IC3-1C)") (class "Default")
      (node (ref "IC3") (pin "18") (pinfunction "1C_18") (pintype "bidirectional"))
      (node (ref "R17") (pin "1") (pinfunction "1_1") (pintype "passive"))
    )
    (net (code "52") (name "Net-(IC3-2C)") (class "Default")
      (node (ref "IC3") (pin "17") (pinfunction "2C_17") (pintype "bidirectional"))
      (node (ref "R18") (pin "1") (pinfunction "1_1") (pintype "passive"))
    )
    (net (code "53") (name "Net-(IC3-3C)") (class "Default")
      (node (ref "IC3") (pin "16") (pinfunction "3C_16") (pintype "bidirectional"))
      (node (ref "R19") (pin "1") (pinfunction "1_1") (pintype "passive"))
    )
    (net (code "54") (name "Net-(IC3-4C)") (class "Default")
      (node (ref "IC3") (pin "15") (pinfunction "4C_15") (pintype "bidirectional"))
      (node (ref "R20") (pin "1") (pinfunction "1_1") (pintype "passive"))
    )
    (net (code "55") (name "Net-(IC3-5C)") (class "Default")
      (node (ref "IC3") (pin "14") (pinfunction "5C_14") (pintype "bidirectional"))
      (node (ref "R21") (pin "1") (pinfunction "1_1") (pintype "passive"))
    )
    (net (code "56") (name "Net-(IC3-6C)") (class "Default")
      (node (ref "IC3") (pin "13") (pinfunction "6C_13") (pintype "bidirectional"))
      (node (ref "R22") (pin "1") (pinfunction "1_1") (pintype "passive"))
    )
    (net (code "57") (name "Net-(IC3-7C)") (class "Default")
      (node (ref "IC3") (pin "12") (pinfunction "7C_12") (pintype "bidirectional"))
      (node (ref "R23") (pin "1") (pinfunction "1_1") (pintype "passive"))
    )
    (net (code "58") (name "Net-(IC3-8C)") (class "Default")
      (node (ref "IC3") (pin "11") (pinfunction "8C_11") (pintype "bidirectional"))
      (node (ref "R24") (pin "1") (pinfunction "1_1") (pintype "passive"))
    )
    (net (code "59") (name "Net-(IC5-DRAIN)") (class "Default")
      (node (ref "IC5") (pin "5") (pinfunction "DRAIN_5") (pintype "input"))
      (node (ref "L6") (pin "2") (pinfunction "2_2") (pintype "passive"))
    )
    (net (code "60") (name "Net-(IC5-SRC)") (class "Default")
      (node (ref "C46") (pin "1") (pinfunction "1_1") (pintype "passive"))
      (node (ref "C51") (pin "1") (pinfunction "1_1") (pintype "passive"))
      (node (ref "C52") (pin "1") (pinfunction "1_1") (pintype "passive"))
      (node (ref "D14") (pin "C") (pinfunction "C_C") (pintype "passive"))
      (node (ref "IC5") (pin "3") (pinfunction "SRC2_3") (pintype "output"))
      (node (ref "IC5") (pin "4") (pinfunction "SRC_4") (pintype "output"))
      (node (ref "L5") (pin "1") (pinfunction "1_1") (pintype "passive"))
      (node (ref "R107") (pin "2") (pinfunction "2_2") (pintype "passive"))
    )
    (net (code "61") (name "Net-(IC5-VCC)") (class "Default")
      (node (ref "C46") (pin "2") (pinfunction "2_2") (pintype "passive"))
      (node (ref "IC5") (pin "1") (pinfunction "VCC_1") (pintype "output"))
      (node (ref "VNI2") (pin "TP") (pinfunction "P$1_TP") (pintype "bidirectional"))
    )
    (net (code "62") (name "Net-(IC6-INN)") (class "Default")
      (node (ref "C25") (pin "1") (pinfunction "1_1") (pintype "passive"))
      (node (ref "IC6") (pin "3") (pinfunction "INN_3") (pintype "input"))
      (node (ref "R34") (pin "2") (pinfunction "2_2") (pintype "passive"))
    )
    (net (code "63") (name "Net-(IC6-INP)") (class "Default")
      (node (ref "C24") (pin "1") (pinfunction "1_1") (pintype "passive"))
      (node (ref "IC6") (pin "2") (pinfunction "INP_2") (pintype "input"))
      (node (ref "R33") (pin "2") (pinfunction "2_2") (pintype "passive"))
    )
    (net (code "64") (name "Net-(IC6-VP)") (class "Default")
      (node (ref "C26") (pin "1") (pinfunction "1_1") (pintype "passive"))
      (node (ref "IC6") (pin "4") (pinfunction "VP_4") (pintype "input"))
      (node (ref "R39") (pin "2") (pinfunction "2_2") (pintype "passive"))
      (node (ref "R40") (pin "1") (pinfunction "1_1") (pintype "passive"))
    )
    (net (code "65") (name "Net-(IC7-INN)") (class "Default")
      (node (ref "C28") (pin "1") (pinfunction "1_1") (pintype "passive"))
      (node (ref "IC7") (pin "3") (pinfunction "INN_3") (pintype "input"))
      (node (ref "R42") (pin "2") (pinfunction "2_2") (pintype "passive"))
    )
    (net (code "66") (name "Net-(IC7-INP)") (class "Default")
      (node (ref "C27") (pin "1") (pinfunction "1_1") (pintype "passive"))
      (node (ref "IC7") (pin "2") (pinfunction "INP_2") (pintype "input"))
      (node (ref "R41") (pin "2") (pinfunction "2_2") (pintype "passive"))
    )
    (net (code "67") (name "Net-(IC7-VP)") (class "Default")
      (node (ref "C29") (pin "1") (pinfunction "1_1") (pintype "passive"))
      (node (ref "IC7") (pin "4") (pinfunction "VP_4") (pintype "input"))
      (node (ref "R47") (pin "2") (pinfunction "2_2") (pintype "passive"))
      (node (ref "R48") (pin "1") (pinfunction "1_1") (pintype "passive"))
    )
    (net (code "68") (name "Net-(IC8-INN)") (class "Default")
      (node (ref "C31") (pin "1") (pinfunction "1_1") (pintype "passive"))
      (node (ref "IC8") (pin "3") (pinfunction "INN_3") (pintype "input"))
      (node (ref "R50") (pin "2") (pinfunction "2_2") (pintype "passive"))
    )
    (net (code "69") (name "Net-(IC8-INP)") (class "Default")
      (node (ref "C30") (pin "1") (pinfunction "1_1") (pintype "passive"))
      (node (ref "IC8") (pin "2") (pinfunction "INP_2") (pintype "input"))
      (node (ref "R49") (pin "2") (pinfunction "2_2") (pintype "passive"))
    )
    (net (code "70") (name "Net-(IC8-VP)") (class "Default")
      (node (ref "C32") (pin "1") (pinfunction "1_1") (pintype "passive"))
      (node (ref "IC8") (pin "4") (pinfunction "VP_4") (pintype "input"))
      (node (ref "R55") (pin "2") (pinfunction "2_2") (pintype "passive"))
      (node (ref "R56") (pin "1") (pinfunction "1_1") (pintype "passive"))
    )
    (net (code "71") (name "Net-(IC9-Y)") (class "Default")
      (node (ref "IC9") (pin "5") (pinfunction "Y_5") (pintype "bidirectional"))
      (node (ref "R91") (pin "1") (pinfunction "1_1") (pintype "passive"))
    )
    (net (code "72") (name "Net-(IC9-~{Y})") (class "Default")
      (node (ref "IC9") (pin "6") (pinfunction "~{Y}_6") (pintype "bidirectional"))
      (node (ref "R92") (pin "1") (pinfunction "1_1") (pintype "passive"))
    )
    (net (code "73") (name "Net-(IC10-INN)") (class "Default")
      (node (ref "C37") (pin "1") (pinfunction "1_1") (pintype "passive"))
      (node (ref "IC10") (pin "3") (pinfunction "INN_3") (pintype "input"))
      (node (ref "R66") (pin "2") (pinfunction "2_2") (pintype "passive"))
    )
    (net (code "74") (name "Net-(IC10-INP)") (class "Default")
      (node (ref "C36") (pin "1") (pinfunction "1_1") (pintype "passive"))
      (node (ref "IC10") (pin "2") (pinfunction "INP_2") (pintype "input"))
      (node (ref "R65") (pin "2") (pinfunction "2_2") (pintype "passive"))
    )
    (net (code "75") (name "Net-(IC10-VP)") (class "Default")
      (node (ref "C38") (pin "1") (pinfunction "1_1") (pintype "passive"))
      (node (ref "IC10") (pin "4") (pinfunction "VP_4") (pintype "input"))
      (node (ref "R71") (pin "2") (pinfunction "2_2") (pintype "passive"))
      (node (ref "R72") (pin "1") (pinfunction "1_1") (pintype "passive"))
    )
    (net (code "76") (name "Net-(IC11-INN)") (class "Default")
      (node (ref "C40") (pin "1") (pinfunction "1_1") (pintype "passive"))
      (node (ref "IC11") (pin "3") (pinfunction "INN_3") (pintype "input"))
      (node (ref "R74") (pin "2") (pinfunction "2_2") (pintype "passive"))
    )
    (net (code "77") (name "Net-(IC11-INP)") (class "Default")
      (node (ref "C39") (pin "1") (pinfunction "1_1") (pintype "passive"))
      (node (ref "IC11") (pin "2") (pinfunction "INP_2") (pintype "input"))
      (node (ref "R73") (pin "2") (pinfunction "2_2") (pintype "passive"))
    )
    (net (code "78") (name "Net-(IC11-VP)") (class "Default")
      (node (ref "C41") (pin "1") (pinfunction "1_1") (pintype "passive"))
      (node (ref "IC11") (pin "4") (pinfunction "VP_4") (pintype "input"))
      (node (ref "R79") (pin "2") (pinfunction "2_2") (pintype "passive"))
      (node (ref "R80") (pin "1") (pinfunction "1_1") (pintype "passive"))
    )
    (net (code "79") (name "Net-(IC12-INN)") (class "Default")
      (node (ref "C43") (pin "1") (pinfunction "1_1") (pintype "passive"))
      (node (ref "IC12") (pin "3") (pinfunction "INN_3") (pintype "input"))
      (node (ref "R82") (pin "2") (pinfunction "2_2") (pintype "passive"))
    )
    (net (code "80") (name "Net-(IC12-INP)") (class "Default")
      (node (ref "C42") (pin "1") (pinfunction "1_1") (pintype "passive"))
      (node (ref "IC12") (pin "2") (pinfunction "INP_2") (pintype "input"))
      (node (ref "R81") (pin "2") (pinfunction "2_2") (pintype "passive"))
    )
    (net (code "81") (name "Net-(IC12-VP)") (class "Default")
      (node (ref "C44") (pin "1") (pinfunction "1_1") (pintype "passive"))
      (node (ref "IC12") (pin "4") (pinfunction "VP_4") (pintype "input"))
      (node (ref "R87") (pin "2") (pinfunction "2_2") (pintype "passive"))
      (node (ref "R88") (pin "1") (pinfunction "1_1") (pintype "passive"))
    )
    (net (code "82") (name "Net-(IC13-DRAIN)") (class "Default")
      (node (ref "IC13") (pin "5") (pinfunction "DRAIN_5") (pintype "input"))
      (node (ref "L4") (pin "2") (pinfunction "2_2") (pintype "passive"))
    )
    (net (code "83") (name "Net-(IC13-SRC)") (class "Default")
      (node (ref "C21") (pin "1") (pinfunction "1_1") (pintype "passive"))
      (node (ref "C22") (pin "1") (pinfunction "1_1") (pintype "passive"))
      (node (ref "C5") (pin "1") (pinfunction "1_1") (pintype "passive"))
      (node (ref "D11") (pin "C") (pinfunction "C_C") (pintype "passive"))
      (node (ref "IC13") (pin "3") (pinfunction "SRC2_3") (pintype "output"))
      (node (ref "IC13") (pin "4") (pinfunction "SRC_4") (pintype "output"))
      (node (ref "L3") (pin "1") (pinfunction "1_1") (pintype "passive"))
      (node (ref "R60") (pin "2") (pinfunction "2_2") (pintype "passive"))
    )
    (net (code "84") (name "Net-(IC13-VCC)") (class "Default")
      (node (ref "C21") (pin "2") (pinfunction "2_2") (pintype "passive"))
      (node (ref "IC13") (pin "1") (pinfunction "VCC_1") (pintype "output"))
      (node (ref "VNI1") (pin "TP") (pinfunction "P$1_TP") (pintype "bidirectional"))
    )
    (net (code "85") (name "Net-(IC14-INN)") (class "Default")
      (node (ref "C49") (pin "1") (pinfunction "1_1") (pintype "passive"))
      (node (ref "IC14") (pin "3") (pinfunction "INN_3") (pintype "input"))
      (node (ref "R98") (pin "2") (pinfunction "2_2") (pintype "passive"))
    )
    (net (code "86") (name "Net-(IC14-INP)") (class "Default")
      (node (ref "C48") (pin "1") (pinfunction "1_1") (pintype "passive"))
      (node (ref "IC14") (pin "2") (pinfunction "INP_2") (pintype "input"))
      (node (ref "R97") (pin "2") (pinfunction "2_2") (pintype "passive"))
    )
    (net (code "87") (name "Net-(IC14-VP)") (class "Default")
      (node (ref "C50") (pin "1") (pinfunction "1_1") (pintype "passive"))
      (node (ref "IC14") (pin "4") (pinfunction "VP_4") (pintype "input"))
      (node (ref "R103") (pin "2") (pinfunction "2_2") (pintype "passive"))
      (node (ref "R104") (pin "1") (pinfunction "1_1") (pintype "passive"))
    )
    (net (code "88") (name "Net-(IC16-INN)") (class "Default")
      (node (ref "C55") (pin "1") (pinfunction "1_1") (pintype "passive"))
      (node (ref "IC16") (pin "3") (pinfunction "INN_3") (pintype "input"))
      (node (ref "R114") (pin "2") (pinfunction "2_2") (pintype "passive"))
    )
    (net (code "89") (name "Net-(IC16-INP)") (class "Default")
      (node (ref "C54") (pin "1") (pinfunction "1_1") (pintype "passive"))
      (node (ref "IC16") (pin "2") (pinfunction "INP_2") (pintype "input"))
      (node (ref "R113") (pin "2") (pinfunction "2_2") (pintype "passive"))
    )
    (net (code "90") (name "Net-(IC16-VP)") (class "Default")
      (node (ref "C56") (pin "1") (pinfunction "1_1") (pintype "passive"))
      (node (ref "IC16") (pin "4") (pinfunction "VP_4") (pintype "input"))
      (node (ref "R119") (pin "2") (pinfunction "2_2") (pintype "passive"))
      (node (ref "R120") (pin "1") (pinfunction "1_1") (pintype "passive"))
    )
    (net (code "91") (name "Net-(OPT1-Pad1)") (class "Default")
      (node (ref "OPT1") (pin "1") (pinfunction "1_1") (pintype "passive"))
      (node (ref "R63") (pin "8") (pinfunction "8_8") (pintype "passive"))
    )
    (net (code "92") (name "Net-(OPT1-Pad3)") (class "Default")
      (node (ref "OPT1") (pin "3") (pinfunction "3_3") (pintype "passive"))
      (node (ref "R63") (pin "7") (pinfunction "7_7") (pintype "passive"))
    )
    (net (code "93") (name "Net-(OPT1-Pad5)") (class "Default")
      (node (ref "OPT1") (pin "5") (pinfunction "5_5") (pintype "passive"))
      (node (ref "R63") (pin "6") (pinfunction "6_6") (pintype "passive"))
    )
    (net (code "94") (name "Net-(OPT1-Pad7)") (class "Default")
      (node (ref "OPT1") (pin "7") (pinfunction "7_7") (pintype "passive"))
      (node (ref "R63") (pin "5") (pinfunction "5_5") (pintype "passive"))
    )
    (net (code "95") (name "Net-(OPT2-Pad1)") (class "Default")
      (node (ref "OPT2") (pin "1") (pinfunction "1_1") (pintype "passive"))
      (node (ref "R110") (pin "8") (pinfunction "8_8") (pintype "passive"))
    )
    (net (code "96") (name "Net-(OPT2-Pad3)") (class "Default")
      (node (ref "OPT2") (pin "3") (pinfunction "3_3") (pintype "passive"))
      (node (ref "R110") (pin "7") (pinfunction "7_7") (pintype "passive"))
    )
    (net (code "97") (name "Net-(OPT3-Pad1)") (class "Default")
      (node (ref "OPT3") (pin "1") (pinfunction "1_1") (pintype "passive"))
      (node (ref "R64") (pin "8") (pinfunction "8_8") (pintype "passive"))
    )
    (net (code "98") (name "Net-(OPT3-Pad3)") (class "Default")
      (node (ref "OPT3") (pin "3") (pinfunction "3_3") (pintype "passive"))
      (node (ref "R64") (pin "7") (pinfunction "7_7") (pintype "passive"))
    )
    (net (code "99") (name "Net-(R36-Pad2)") (class "Default")
      (node (ref "R36") (pin "2") (pinfunction "2_2") (pintype "passive"))
      (node (ref "R37") (pin "1") (pinfunction "1_1") (pintype "passive"))
    )
    (net (code "100") (name "Net-(R37-Pad2)") (class "Default")
      (node (ref "R37") (pin "2") (pinfunction "2_2") (pintype "passive"))
      (node (ref "R38") (pin "1") (pinfunction "1_1") (pintype "passive"))
    )
    (net (code "101") (name "Net-(R38-Pad2)") (class "Default")
      (node (ref "R38") (pin "2") (pinfunction "2_2") (pintype "passive"))
      (node (ref "R39") (pin "1") (pinfunction "1_1") (pintype "passive"))
    )
    (net (code "102") (name "Net-(R44-Pad2)") (class "Default")
      (node (ref "R44") (pin "2") (pinfunction "2_2") (pintype "passive"))
      (node (ref "R45") (pin "1") (pinfunction "1_1") (pintype "passive"))
    )
    (net (code "103") (name "Net-(R45-Pad2)") (class "Default")
      (node (ref "R45") (pin "2") (pinfunction "2_2") (pintype "passive"))
      (node (ref "R46") (pin "1") (pinfunction "1_1") (pintype "passive"))
    )
    (net (code "104") (name "Net-(R46-Pad2)") (class "Default")
      (node (ref "R46") (pin "2") (pinfunction "2_2") (pintype "passive"))
      (node (ref "R47") (pin "1") (pinfunction "1_1") (pintype "passive"))
    )
    (net (code "105") (name "Net-(R52-Pad2)") (class "Default")
      (node (ref "R52") (pin "2") (pinfunction "2_2") (pintype "passive"))
      (node (ref "R53") (pin "1") (pinfunction "1_1") (pintype "passive"))
    )
    (net (code "106") (name "Net-(R53-Pad2)") (class "Default")
      (node (ref "R53") (pin "2") (pinfunction "2_2") (pintype "passive"))
      (node (ref "R54") (pin "1") (pinfunction "1_1") (pintype "passive"))
    )
    (net (code "107") (name "Net-(R54-Pad2)") (class "Default")
      (node (ref "R54") (pin "2") (pinfunction "2_2") (pintype "passive"))
      (node (ref "R55") (pin "1") (pinfunction "1_1") (pintype "passive"))
    )
    (net (code "108") (name "Net-(R68-Pad2)") (class "Default")
      (node (ref "R68") (pin "2") (pinfunction "2_2") (pintype "passive"))
      (node (ref "R69") (pin "1") (pinfunction "1_1") (pintype "passive"))
    )
    (net (code "109") (name "Net-(R69-Pad2)") (class "Default")
      (node (ref "R69") (pin "2") (pinfunction "2_2") (pintype "passive"))
      (node (ref "R70") (pin "1") (pinfunction "1_1") (pintype "passive"))
    )
    (net (code "110") (name "Net-(R70-Pad2)") (class "Default")
      (node (ref "R70") (pin "2") (pinfunction "2_2") (pintype "passive"))
      (node (ref "R71") (pin "1") (pinfunction "1_1") (pintype "passive"))
    )
    (net (code "111") (name "Net-(R76-Pad2)") (class "Default")
      (node (ref "R76") (pin "2") (pinfunction "2_2") (pintype "passive"))
      (node (ref "R77") (pin "1") (pinfunction "1_1") (pintype "passive"))
    )
    (net (code "112") (name "Net-(R77-Pad2)") (class "Default")
      (node (ref "R77") (pin "2") (pinfunction "2_2") (pintype "passive"))
      (node (ref "R78") (pin "1") (pinfunction "1_1") (pintype "passive"))
    )
    (net (code "113") (name "Net-(R78-Pad2)") (class "Default")
      (node (ref "R78") (pin "2") (pinfunction "2_2") (pintype "passive"))
      (node (ref "R79") (pin "1") (pinfunction "1_1") (pintype "passive"))
    )
    (net (code "114") (name "Net-(R84-Pad2)") (class "Default")
      (node (ref "R84") (pin "2") (pinfunction "2_2") (pintype "passive"))
      (node (ref "R85") (pin "1") (pinfunction "1_1") (pintype "passive"))
    )
    (net (code "115") (name "Net-(R85-Pad2)") (class "Default")
      (node (ref "R85") (pin "2") (pinfunction "2_2") (pintype "passive"))
      (node (ref "R86") (pin "1") (pinfunction "1_1") (pintype "passive"))
    )
    (net (code "116") (name "Net-(R86-Pad2)") (class "Default")
      (node (ref "R86") (pin "2") (pinfunction "2_2") (pintype "passive"))
      (node (ref "R87") (pin "1") (pinfunction "1_1") (pintype "passive"))
    )
    (net (code "117") (name "Net-(R100-Pad2)") (class "Default")
      (node (ref "R100") (pin "2") (pinfunction "2_2") (pintype "passive"))
      (node (ref "R101") (pin "1") (pinfunction "1_1") (pintype "passive"))
    )
    (net (code "118") (name "Net-(R101-Pad2)") (class "Default")
      (node (ref "R101") (pin "2") (pinfunction "2_2") (pintype "passive"))
      (node (ref "R102") (pin "1") (pinfunction "1_1") (pintype "passive"))
    )
    (net (code "119") (name "Net-(R102-Pad2)") (class "Default")
      (node (ref "R102") (pin "2") (pinfunction "2_2") (pintype "passive"))
      (node (ref "R103") (pin "1") (pinfunction "1_1") (pintype "passive"))
    )
    (net (code "120") (name "Net-(R116-Pad2)") (class "Default")
      (node (ref "R116") (pin "2") (pinfunction "2_2") (pintype "passive"))
      (node (ref "R117") (pin "1") (pinfunction "1_1") (pintype "passive"))
    )
    (net (code "121") (name "Net-(R117-Pad2)") (class "Default")
      (node (ref "R117") (pin "2") (pinfunction "2_2") (pintype "passive"))
      (node (ref "R118") (pin "1") (pinfunction "1_1") (pintype "passive"))
    )
    (net (code "122") (name "Net-(R118-Pad2)") (class "Default")
      (node (ref "R118") (pin "2") (pinfunction "2_2") (pintype "passive"))
      (node (ref "R119") (pin "1") (pinfunction "1_1") (pintype "passive"))
    )
    (net (code "123") (name "OUT_1") (class "Default")
      (node (ref "K1") (pin "4") (pinfunction "4_4") (pintype "passive"))
      (node (ref "K1") (pin "5") (pinfunction "5_5") (pintype "passive"))
      (node (ref "R25") (pin "1") (pinfunction "1_1") (pintype "passive"))
      (node (ref "R34") (pin "1") (pinfunction "1_1") (pintype "passive"))
      (node (ref "R35") (pin "1") (pinfunction "1_1") (pintype "passive"))
      (node (ref "R36") (pin "1") (pinfunction "1_1") (pintype "passive"))
    )
    (net (code "124") (name "OUT_2") (class "Default")
      (node (ref "K2") (pin "4") (pinfunction "4_4") (pintype "passive"))
      (node (ref "K2") (pin "5") (pinfunction "5_5") (pintype "passive"))
      (node (ref "R32") (pin "1") (pinfunction "1_1") (pintype "passive"))
      (node (ref "R50") (pin "1") (pinfunction "1_1") (pintype "passive"))
      (node (ref "R51") (pin "1") (pinfunction "1_1") (pintype "passive"))
      (node (ref "R52") (pin "1") (pinfunction "1_1") (pintype "passive"))
    )
    (net (code "125") (name "OUT_3") (class "Default")
      (node (ref "K3") (pin "4") (pinfunction "4_4") (pintype "passive"))
      (node (ref "K3") (pin "5") (pinfunction "5_5") (pintype "passive"))
      (node (ref "R31") (pin "1") (pinfunction "1_1") (pintype "passive"))
      (node (ref "R66") (pin "1") (pinfunction "1_1") (pintype "passive"))
      (node (ref "R67") (pin "1") (pinfunction "1_1") (pintype "passive"))
      (node (ref "R68") (pin "1") (pinfunction "1_1") (pintype "passive"))
    )
    (net (code "126") (name "OUT_4") (class "Default")
      (node (ref "K4") (pin "4") (pinfunction "4_4") (pintype "passive"))
      (node (ref "K4") (pin "5") (pinfunction "5_5") (pintype "passive"))
      (node (ref "R30") (pin "1") (pinfunction "1_1") (pintype "passive"))
      (node (ref "R82") (pin "1") (pinfunction "1_1") (pintype "passive"))
      (node (ref "R83") (pin "1") (pinfunction "1_1") (pintype "passive"))
      (node (ref "R84") (pin "1") (pinfunction "1_1") (pintype "passive"))
    )
    (net (code "127") (name "OUT_5") (class "Default")
      (node (ref "K5") (pin "4") (pinfunction "4_4") (pintype "passive"))
      (node (ref "K5") (pin "5") (pinfunction "5_5") (pintype "passive"))
      (node (ref "R26") (pin "1") (pinfunction "1_1") (pintype "passive"))
      (node (ref "R42") (pin "1") (pinfunction "1_1") (pintype "passive"))
      (node (ref "R43") (pin "1") (pinfunction "1_1") (pintype "passive"))
      (node (ref "R44") (pin "1") (pinfunction "1_1") (pintype "passive"))
    )
    (net (code "128") (name "OUT_6") (class "Default")
      (node (ref "K6") (pin "4") (pinfunction "4_4") (pintype "passive"))
      (node (ref "K6") (pin "5") (pinfunction "5_5") (pintype "passive"))
      (node (ref "R27") (pin "1") (pinfunction "1_1") (pintype "passive"))
      (node (ref "R74") (pin "1") (pinfunction "1_1") (pintype "passive"))
      (node (ref "R75") (pin "1") (pinfunction "1_1") (pintype "passive"))
      (node (ref "R76") (pin "1") (pinfunction "1_1") (pintype "passive"))
    )
    (net (code "129") (name "OUT_7") (class "Default")
      (node (ref "K7") (pin "4") (pinfunction "4_4") (pintype "passive"))
      (node (ref "K7") (pin "5") (pinfunction "5_5") (pintype "passive"))
      (node (ref "R100") (pin "1") (pinfunction "1_1") (pintype "passive"))
      (node (ref "R28") (pin "1") (pinfunction "1_1") (pintype "passive"))
      (node (ref "R98") (pin "1") (pinfunction "1_1") (pintype "passive"))
      (node (ref "R99") (pin "1") (pinfunction "1_1") (pintype "passive"))
    )
    (net (code "130") (name "OUT_8") (class "Default")
      (node (ref "K8") (pin "4") (pinfunction "4_4") (pintype "passive"))
      (node (ref "K8") (pin "5") (pinfunction "5_5") (pintype "passive"))
      (node (ref "R114") (pin "1") (pinfunction "1_1") (pintype "passive"))
      (node (ref "R115") (pin "1") (pinfunction "1_1") (pintype "passive"))
      (node (ref "R116") (pin "1") (pinfunction "1_1") (pintype "passive"))
      (node (ref "R29") (pin "1") (pinfunction "1_1") (pintype "passive"))
    )
    (net (code "131") (name "RELAY_1") (class "Default")
      (node (ref "D1") (pin "A") (pinfunction "A_A") (pintype "passive"))
      (node (ref "K1") (pin "1") (pinfunction "1_1") (pintype "passive"))
      (node (ref "R24") (pin "2") (pinfunction "2_2") (pintype "passive"))
    )
    (net (code "132") (name "RELAY_2") (class "Default")
      (node (ref "D2") (pin "A") (pinfunction "A_A") (pintype "passive"))
      (node (ref "K2") (pin "1") (pinfunction "1_1") (pintype "passive"))
      (node (ref "R23") (pin "2") (pinfunction "2_2") (pintype "passive"))
    )
    (net (code "133") (name "RELAY_3") (class "Default")
      (node (ref "D3") (pin "A") (pinfunction "A_A") (pintype "passive"))
      (node (ref "K3") (pin "1") (pinfunction "1_1") (pintype "passive"))
      (node (ref "R22") (pin "2") (pinfunction "2_2") (pintype "passive"))
    )
    (net (code "134") (name "RELAY_4") (class "Default")
      (node (ref "D4") (pin "A") (pinfunction "A_A") (pintype "passive"))
      (node (ref "K4") (pin "1") (pinfunction "1_1") (pintype "passive"))
      (node (ref "R21") (pin "2") (pinfunction "2_2") (pintype "passive"))
    )
    (net (code "135") (name "RELAY_5") (class "Default")
      (node (ref "D5") (pin "A") (pinfunction "A_A") (pintype "passive"))
      (node (ref "K5") (pin "1") (pinfunction "1_1") (pintype "passive"))
      (node (ref "R20") (pin "2") (pinfunction "2_2") (pintype "passive"))
    )
    (net (code "136") (name "RELAY_6") (class "Default")
      (node (ref "D6") (pin "A") (pinfunction "A_A") (pintype "passive"))
      (node (ref "K6") (pin "1") (pinfunction "1_1") (pintype "passive"))
      (node (ref "R19") (pin "2") (pinfunction "2_2") (pintype "passive"))
    )
    (net (code "137") (name "RELAY_7") (class "Default")
      (node (ref "D7") (pin "A") (pinfunction "A_A") (pintype "passive"))
      (node (ref "K7") (pin "1") (pinfunction "1_1") (pintype "passive"))
      (node (ref "R18") (pin "2") (pinfunction "2_2") (pintype "passive"))
    )
    (net (code "138") (name "RELAY_8") (class "Default")
      (node (ref "D8") (pin "A") (pinfunction "A_A") (pintype "passive"))
      (node (ref "K8") (pin "1") (pinfunction "1_1") (pintype "passive"))
      (node (ref "R17") (pin "2") (pinfunction "2_2") (pintype "passive"))
    )
    (net (code "139") (name "REL_0") (class "Default")
      (node (ref "IC3") (pin "8") (pinfunction "8B_8") (pintype "bidirectional"))
      (node (ref "IC4") (pin "17") (pinfunction "IO1.0_17") (pintype "bidirectional"))
    )
    (net (code "140") (name "REL_1") (class "Default")
      (node (ref "IC3") (pin "7") (pinfunction "7B_7") (pintype "bidirectional"))
      (node (ref "IC4") (pin "18") (pinfunction "IO1.1_18") (pintype "bidirectional"))
    )
    (net (code "141") (name "REL_2") (class "Default")
      (node (ref "IC3") (pin "6") (pinfunction "6B_6") (pintype "bidirectional"))
      (node (ref "IC4") (pin "19") (pinfunction "IO1.2_19") (pintype "bidirectional"))
    )
    (net (code "142") (name "REL_3") (class "Default")
      (node (ref "IC3") (pin "5") (pinfunction "5B_5") (pintype "bidirectional"))
      (node (ref "IC4") (pin "20") (pinfunction "IO1.3_20") (pintype "bidirectional"))
    )
    (net (code "143") (name "REL_4") (class "Default")
      (node (ref "IC3") (pin "4") (pinfunction "4B_4") (pintype "bidirectional"))
      (node (ref "IC4") (pin "21") (pinfunction "IO1.4_21") (pintype "bidirectional"))
    )
    (net (code "144") (name "REL_5") (class "Default")
      (node (ref "IC3") (pin "3") (pinfunction "3B_3") (pintype "bidirectional"))
      (node (ref "IC4") (pin "22") (pinfunction "IO1.5_22") (pintype "bidirectional"))
    )
    (net (code "145") (name "REL_6") (class "Default")
      (node (ref "IC3") (pin "2") (pinfunction "2B_2") (pintype "bidirectional"))
      (node (ref "IC4") (pin "23") (pinfunction "IO1.6_23") (pintype "bidirectional"))
    )
    (net (code "146") (name "REL_7") (class "Default")
      (node (ref "IC3") (pin "1") (pinfunction "1B_1") (pintype "bidirectional"))
      (node (ref "IC4") (pin "24") (pinfunction "IO1.7_24") (pintype "bidirectional"))
    )
    (net (code "147") (name "RX_CH1") (class "Default")
      (node (ref "IC6") (pin "8") (pinfunction "RX_8") (pintype "bidirectional"))
    )
    (net (code "148") (name "RX_CH2") (class "Default")
      (node (ref "IC8") (pin "8") (pinfunction "RX_8") (pintype "bidirectional"))
    )
    (net (code "149") (name "RX_CH3") (class "Default")
      (node (ref "IC10") (pin "8") (pinfunction "RX_8") (pintype "bidirectional"))
    )
    (net (code "150") (name "RX_CH4") (class "Default")
      (node (ref "IC12") (pin "8") (pinfunction "RX_8") (pintype "bidirectional"))
    )
    (net (code "151") (name "RX_CH5") (class "Default")
      (node (ref "IC7") (pin "8") (pinfunction "RX_8") (pintype "bidirectional"))
    )
    (net (code "152") (name "RX_CH6") (class "Default")
      (node (ref "IC11") (pin "8") (pinfunction "RX_8") (pintype "bidirectional"))
    )
    (net (code "153") (name "RX_CH7") (class "Default")
      (node (ref "IC14") (pin "8") (pinfunction "RX_8") (pintype "bidirectional"))
    )
    (net (code "154") (name "RX_CH8") (class "Default")
      (node (ref "IC16") (pin "8") (pinfunction "RX_8") (pintype "bidirectional"))
    )
    (net (code "155") (name "TX_CH1") (class "Default")
      (node (ref "IC6") (pin "6") (pinfunction "TX_6") (pintype "bidirectional"))
      (node (ref "OPT1") (pin "8") (pinfunction "8_8") (pintype "passive"))
    )
    (net (code "156") (name "TX_CH2") (class "Default")
      (node (ref "IC8") (pin "6") (pinfunction "TX_6") (pintype "bidirectional"))
      (node (ref "OPT1") (pin "6") (pinfunction "6_6") (pintype "passive"))
    )
    (net (code "157") (name "TX_CH3") (class "Default")
      (node (ref "IC10") (pin "6") (pinfunction "TX_6") (pintype "bidirectional"))
      (node (ref "OPT1") (pin "4") (pinfunction "4_4") (pintype "passive"))
    )
    (net (code "158") (name "TX_CH4") (class "Default")
      (node (ref "IC12") (pin "6") (pinfunction "TX_6") (pintype "bidirectional"))
      (node (ref "OPT1") (pin "2") (pinfunction "2_2") (pintype "passive"))
    )
    (net (code "159") (name "TX_CH5") (class "Default")
      (node (ref "IC7") (pin "6") (pinfunction "TX_6") (pintype "bidirectional"))
      (node (ref "OPT3") (pin "2") (pinfunction "2_2") (pintype "passive"))
    )
    (net (code "160") (name "TX_CH6") (class "Default")
      (node (ref "IC11") (pin "6") (pinfunction "TX_6") (pintype "bidirectional"))
      (node (ref "OPT3") (pin "4") (pinfunction "4_4") (pintype "passive"))
    )
    (net (code "161") (name "TX_CH7") (class "Default")
      (node (ref "IC14") (pin "6") (pinfunction "TX_6") (pintype "bidirectional"))
      (node (ref "OPT2") (pin "2") (pinfunction "2_2") (pintype "passive"))
    )
    (net (code "162") (name "TX_CH8") (class "Default")
      (node (ref "IC16") (pin "6") (pinfunction "TX_6") (pintype "bidirectional"))
      (node (ref "OPT2") (pin "4") (pinfunction "4_4") (pintype "passive"))
    )
    (net (code "163") (name "TX_MUX1") (class "Default")
      (node (ref "IC9") (pin "4") (pinfunction "D0_4") (pintype "bidirectional"))
      (node (ref "OPT1") (pin "10") (pinfunction "10_10") (pintype "passive"))
      (node (ref "R89") (pin "4") (pinfunction "4_4") (pintype "passive"))
    )
    (net (code "164") (name "TX_MUX2") (class "Default")
      (node (ref "IC9") (pin "3") (pinfunction "D1_3") (pintype "bidirectional"))
      (node (ref "OPT1") (pin "12") (pinfunction "12_12") (pintype "passive"))
      (node (ref "R89") (pin "3") (pinfunction "3_3") (pintype "passive"))
    )
    (net (code "165") (name "TX_MUX3") (class "Default")
      (node (ref "IC9") (pin "2") (pinfunction "D2_2") (pintype "bidirectional"))
      (node (ref "OPT1") (pin "14") (pinfunction "14_14") (pintype "passive"))
      (node (ref "R89") (pin "2") (pinfunction "2_2") (pintype "passive"))
    )
    (net (code "166") (name "TX_MUX4") (class "Default")
      (node (ref "IC9") (pin "1") (pinfunction "D3_1") (pintype "bidirectional"))
      (node (ref "OPT1") (pin "16") (pinfunction "16_16") (pintype "passive"))
      (node (ref "R89") (pin "1") (pinfunction "1_1") (pintype "passive"))
    )
    (net (code "167") (name "TX_MUX5") (class "Default")
      (node (ref "IC9") (pin "15") (pinfunction "D4_15") (pintype "bidirectional"))
      (node (ref "OPT3") (pin "8") (pinfunction "8_8") (pintype "passive"))
      (node (ref "R90") (pin "1") (pinfunction "1_1") (pintype "passive"))
    )
    (net (code "168") (name "TX_MUX6") (class "Default")
      (node (ref "IC9") (pin "14") (pinfunction "D5_14") (pintype "bidirectional"))
      (node (ref "OPT3") (pin "6") (pinfunction "6_6") (pintype "passive"))
      (node (ref "R90") (pin "2") (pinfunction "2_2") (pintype "passive"))
    )
    (net (code "169") (name "TX_MUX7") (class "Default")
      (node (ref "IC9") (pin "13") (pinfunction "D6_13") (pintype "bidirectional"))
      (node (ref "OPT2") (pin "8") (pinfunction "8_8") (pintype "passive"))
      (node (ref "R90") (pin "3") (pinfunction "3_3") (pintype "passive"))
    )
    (net (code "170") (name "TX_MUX8") (class "Default")
      (node (ref "IC9") (pin "12") (pinfunction "D7_12") (pintype "bidirectional"))
      (node (ref "OPT2") (pin "6") (pinfunction "6_6") (pintype "passive"))
      (node (ref "R90") (pin "4") (pinfunction "4_4") (pintype "passive"))
    )
    (net (code "171") (name "UART0_RX") (class "Default")
      (node (ref "J1") (pin "10") (pinfunction "10_10") (pintype "bidirectional"))
    )
    (net (code "172") (name "UART0_TX") (class "Default")
      (node (ref "J1") (pin "11") (pinfunction "11_11") (pintype "bidirectional"))
      (node (ref "R91") (pin "2") (pinfunction "2_2") (pintype "passive"))
      (node (ref "R92") (pin "2") (pinfunction "2_2") (pintype "passive"))
    )
    (net (code "173") (name "unconnected-(IC4-INTA-Pad16)") (class "Default")
      (node (ref "IC4") (pin "16") (pinfunction "INTA_16") (pintype "bidirectional"))
    )
    (net (code "174") (name "unconnected-(IC4-INTB-Pad15)") (class "Default")
      (node (ref "IC4") (pin "15") (pinfunction "INTB_15") (pintype "bidirectional"))
    )
    (net (code "175") (name "unconnected-(IC4-IO2.4-Pad1)") (class "Default")
      (node (ref "IC4") (pin "1") (pinfunction "IO2.4_1") (pintype "bidirectional"))
    )
    (net (code "176") (name "unconnected-(IC4-IO2.5-Pad2)") (class "Default")
      (node (ref "IC4") (pin "2") (pinfunction "IO2.5_2") (pintype "bidirectional"))
    )
    (net (code "177") (name "unconnected-(IC4-IO2.6-Pad3)") (class "Default")
      (node (ref "IC4") (pin "3") (pinfunction "IO2.6_3") (pintype "bidirectional"))
    )
    (net (code "178") (name "unconnected-(IC4-IO2.7-Pad4)") (class "Default")
      (node (ref "IC4") (pin "4") (pinfunction "IO2.7_4") (pintype "bidirectional"))
    )
    (net (code "179") (name "unconnected-(IC6-PF-Pad7)") (class "Default")
      (node (ref "IC6") (pin "7") (pinfunction "PF_7") (pintype "bidirectional"))
    )
    (net (code "180") (name "unconnected-(IC7-PF-Pad7)") (class "Default")
      (node (ref "IC7") (pin "7") (pinfunction "PF_7") (pintype "bidirectional"))
    )
    (net (code "181") (name "unconnected-(IC8-PF-Pad7)") (class "Default")
      (node (ref "IC8") (pin "7") (pinfunction "PF_7") (pintype "bidirectional"))
    )
    (net (code "182") (name "unconnected-(IC10-PF-Pad7)") (class "Default")
      (node (ref "IC10") (pin "7") (pinfunction "PF_7") (pintype "bidirectional"))
    )
    (net (code "183") (name "unconnected-(IC11-PF-Pad7)") (class "Default")
      (node (ref "IC11") (pin "7") (pinfunction "PF_7") (pintype "bidirectional"))
    )
    (net (code "184") (name "unconnected-(IC12-PF-Pad7)") (class "Default")
      (node (ref "IC12") (pin "7") (pinfunction "PF_7") (pintype "bidirectional"))
    )
    (net (code "185") (name "unconnected-(IC14-PF-Pad7)") (class "Default")
      (node (ref "IC14") (pin "7") (pinfunction "PF_7") (pintype "bidirectional"))
    )
    (net (code "186") (name "unconnected-(IC16-PF-Pad7)") (class "Default")
      (node (ref "IC16") (pin "7") (pinfunction "PF_7") (pintype "bidirectional"))
    )
    (net (code "187") (name "unconnected-(J1-Pad17)") (class "Default")
      (node (ref "J1") (pin "17") (pinfunction "17_17") (pintype "bidirectional"))
    )
    (net (code "188") (name "unconnected-(J1-Pad18)") (class "Default")
      (node (ref "J1") (pin "18") (pinfunction "18_18") (pintype "bidirectional"))
    )
    (net (code "189") (name "unconnected-(J1-Pad19)") (class "Default")
      (node (ref "J1") (pin "19") (pinfunction "19_19") (pintype "bidirectional"))
    )
    (net (code "190") (name "unconnected-(J1-Pad20)") (class "Default")
      (node (ref "J1") (pin "20") (pinfunction "20_20") (pintype "bidirectional"))
    )
    (net (code "191") (name "unconnected-(R64-Pad5)") (class "Default")
      (node (ref "R64") (pin "5") (pinfunction "5_5") (pintype "passive"))
    )
    (net (code "192") (name "unconnected-(R64-Pad6)") (class "Default")
      (node (ref "R64") (pin "6") (pinfunction "6_6") (pintype "passive"))
    )
    (net (code "193") (name "unconnected-(R110-Pad5)") (class "Default")
      (node (ref "R110") (pin "5") (pinfunction "5_5") (pintype "passive"))
    )
    (net (code "194") (name "unconnected-(R110-Pad6)") (class "Default")
      (node (ref "R110") (pin "6") (pinfunction "6_6") (pintype "passive"))
    )
  )
)
